# DUT.net
KiCad netlist of a schematic drawn in Altium Designer
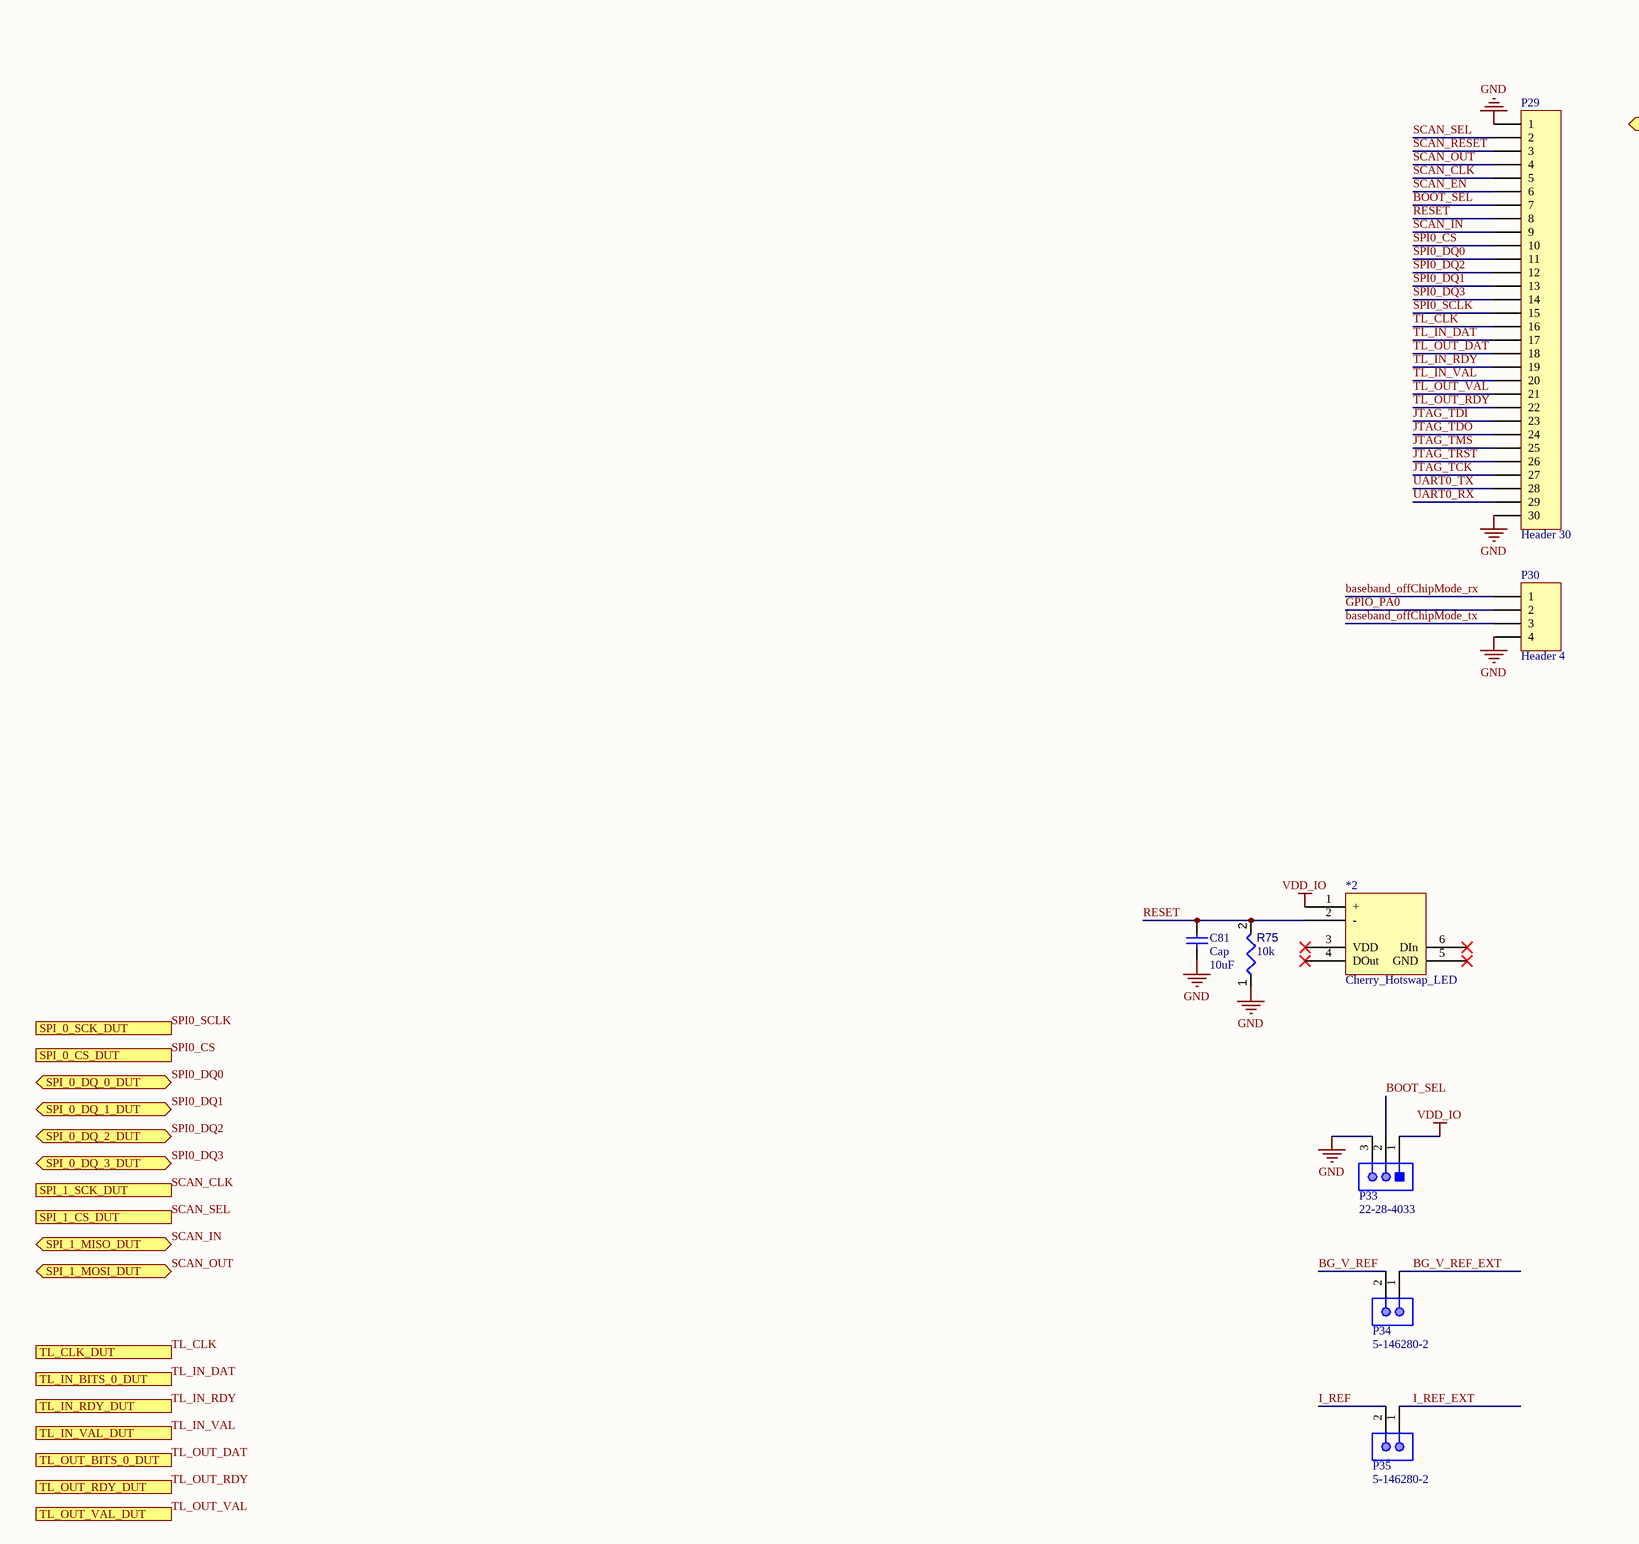
[diagram p0: DUT.SchDoc, top left]
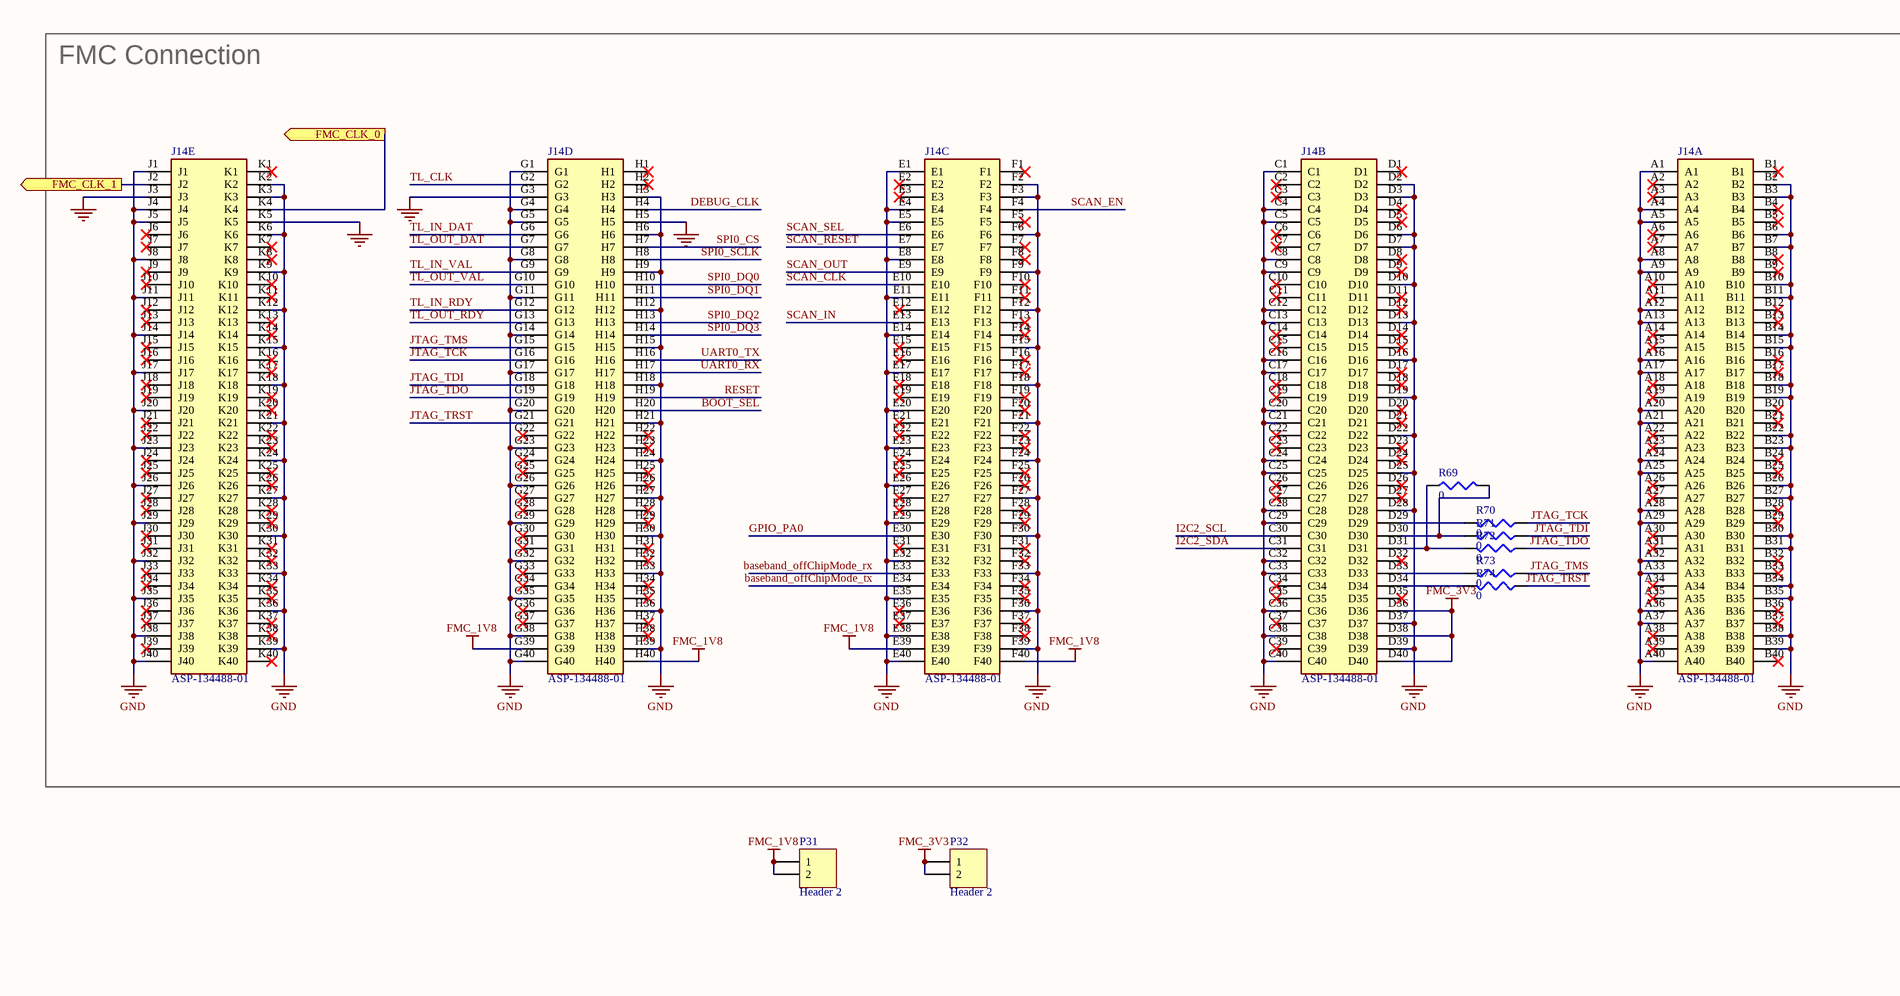
[diagram p1: DUT.SchDoc, top right]
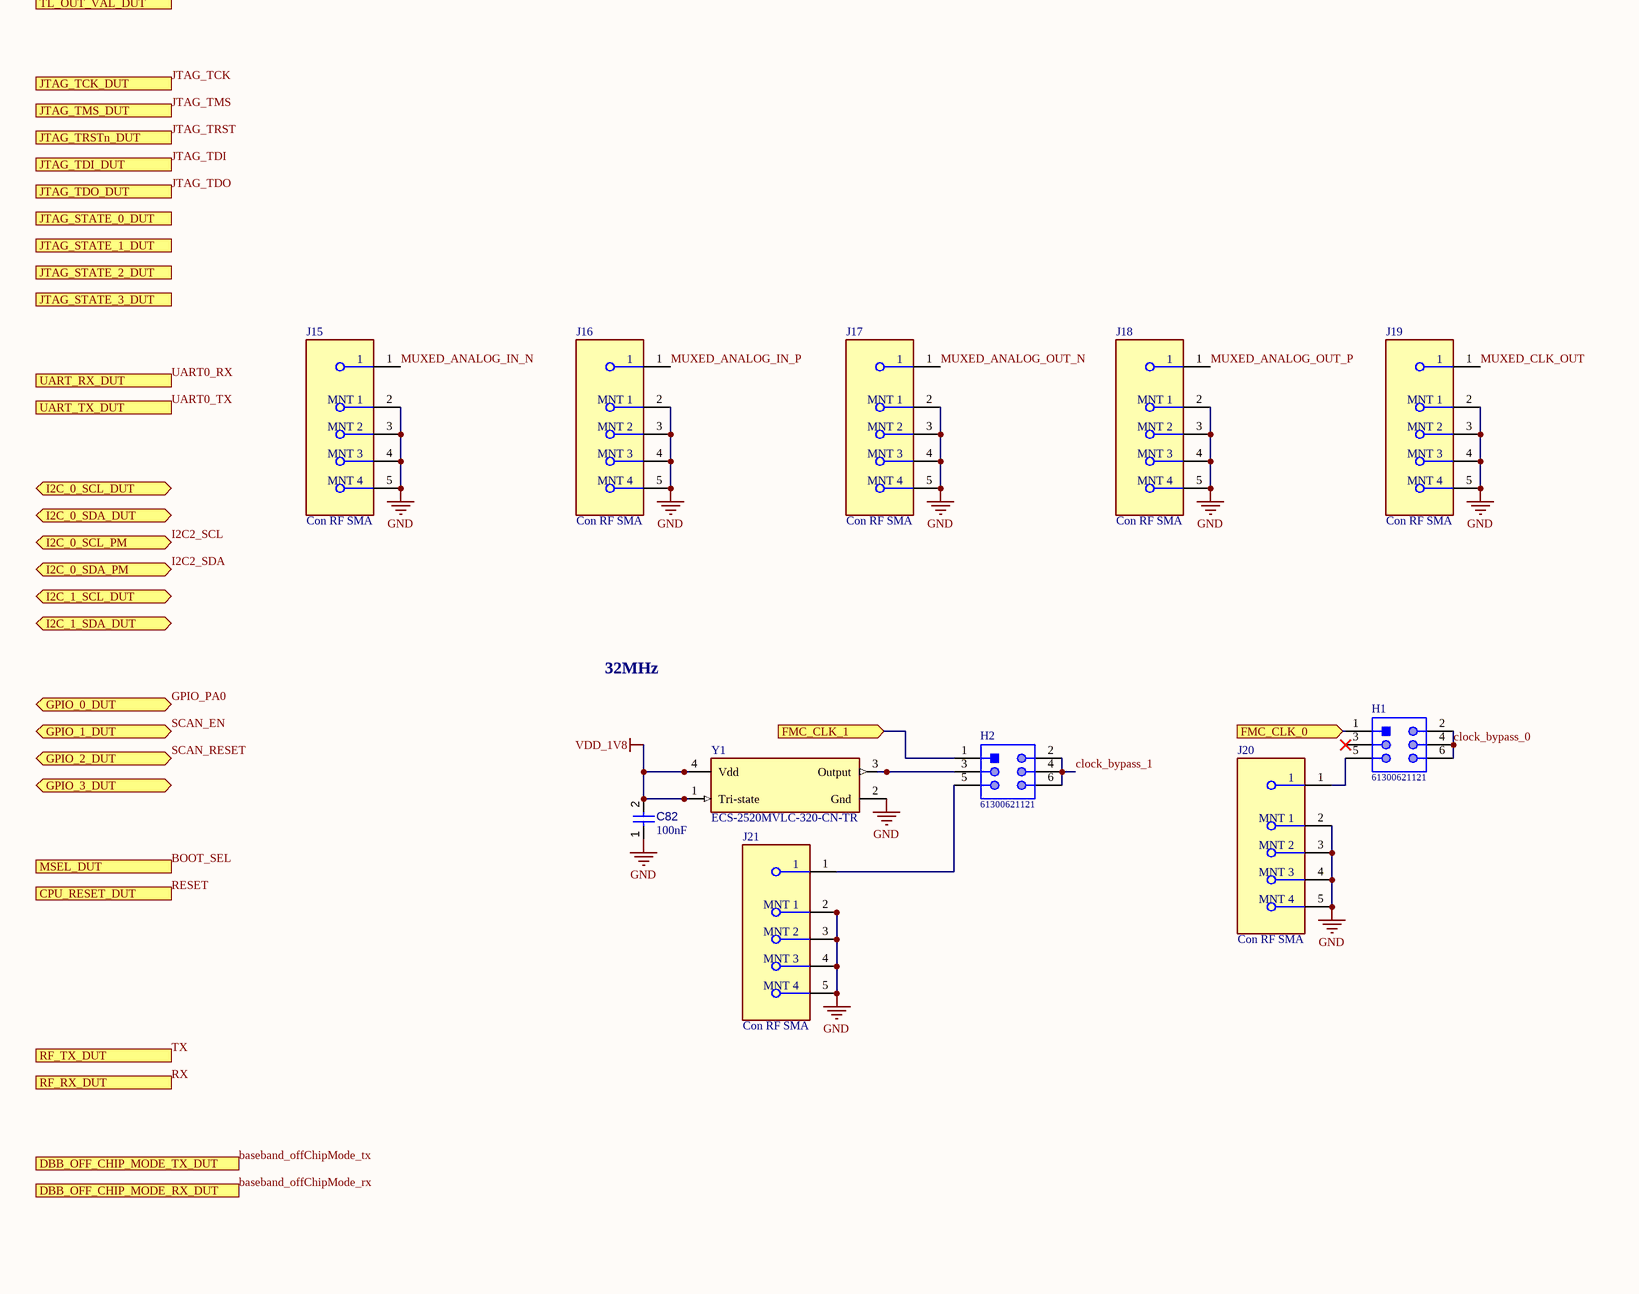
[diagram p2: DUT.SchDoc, bottom left]
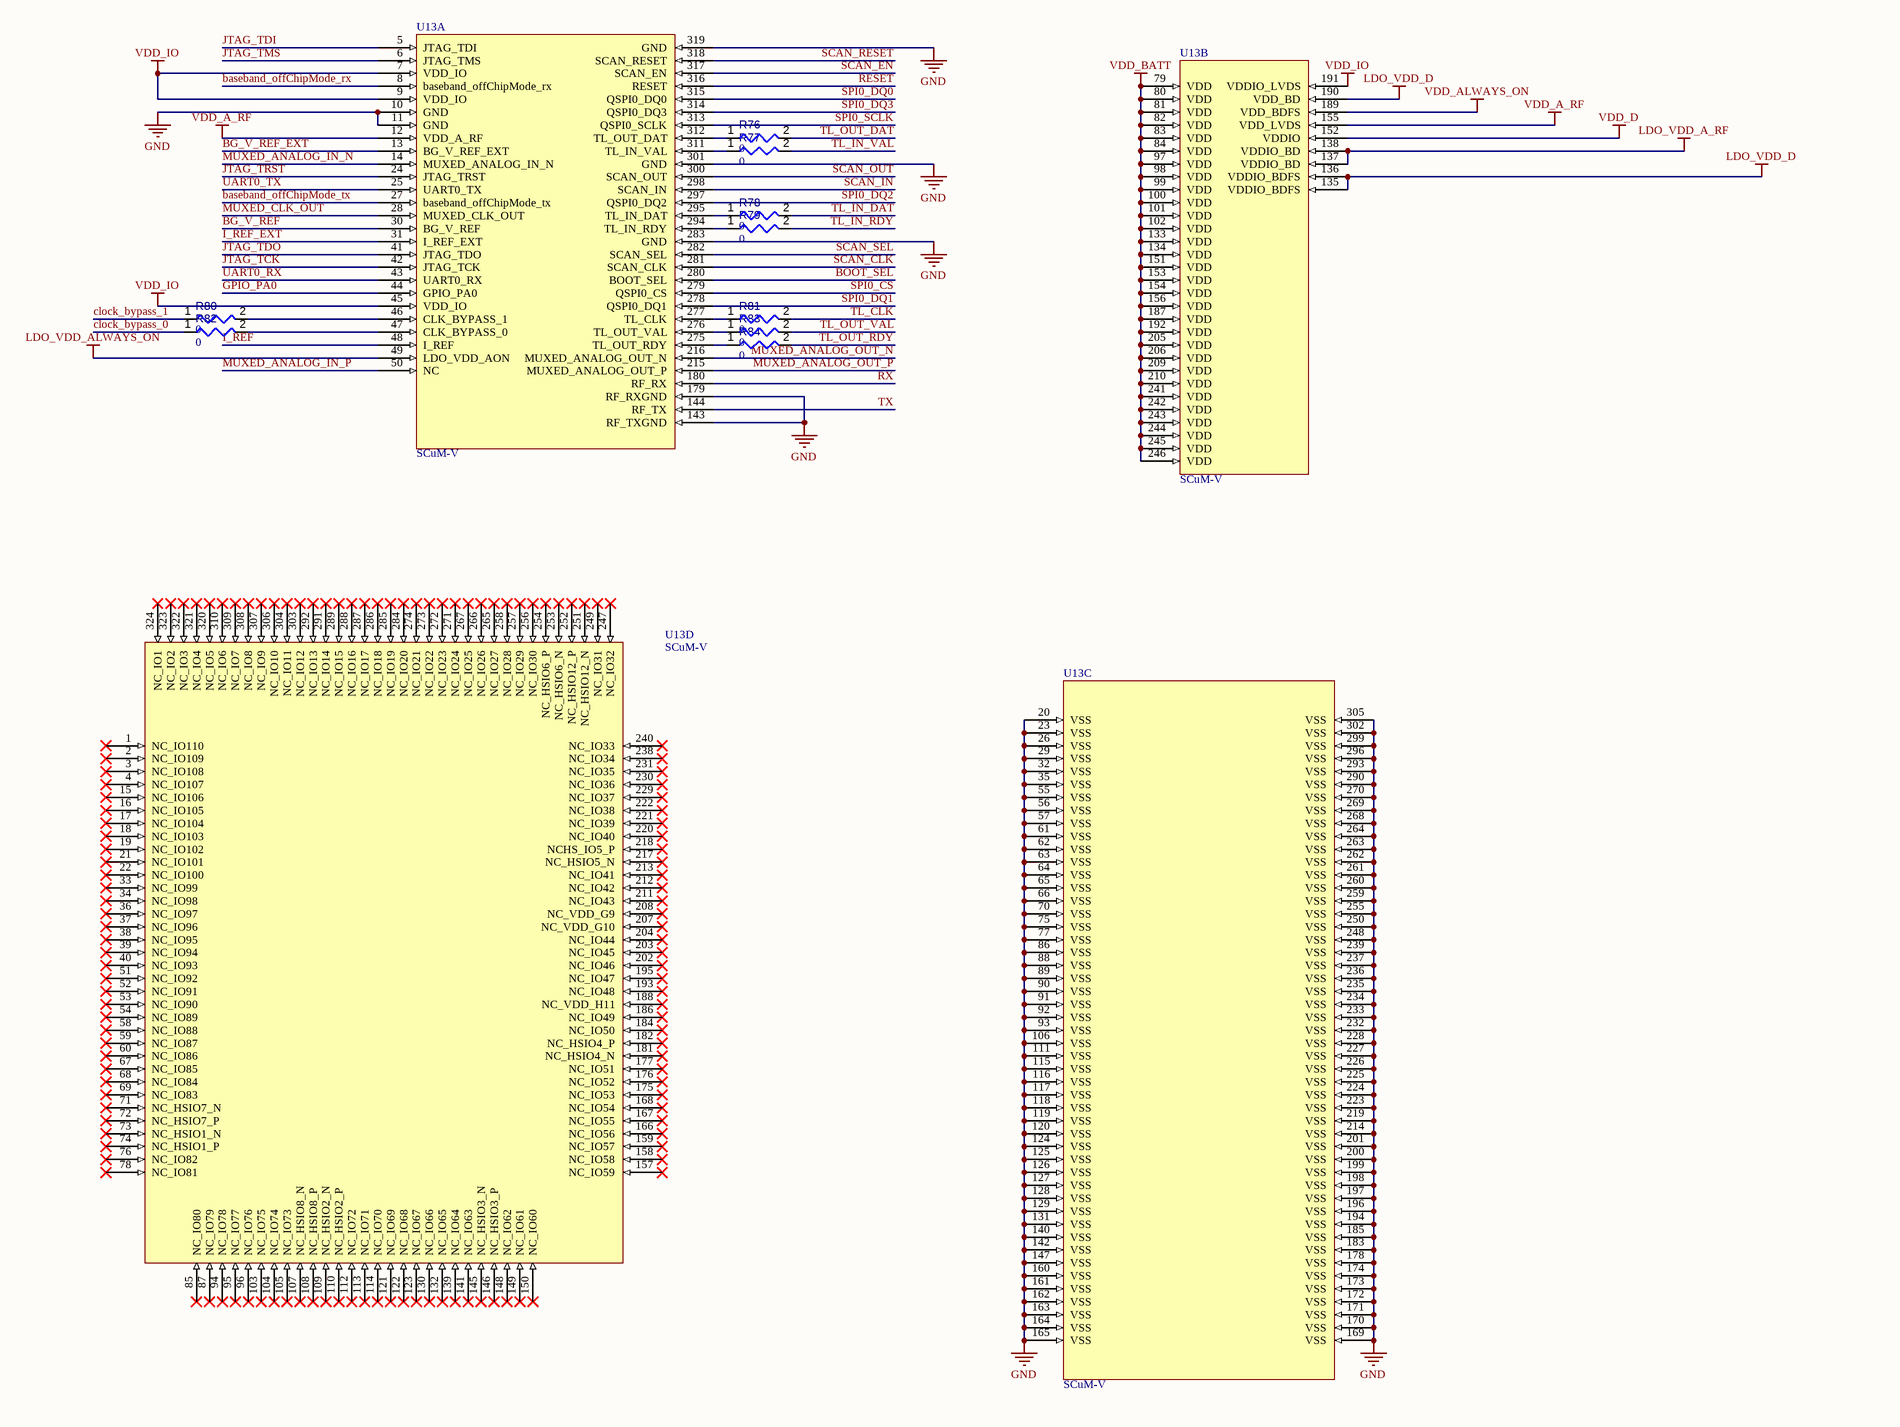
[diagram p3: DUT.SchDoc, bottom right]

(export (version "E")
  (design (tool "Eeschema 10.0.6"))
  (components
    (comp (ref "*2")
      (value "Cherry_Hotswap_LED")
      (footprint "New footprint 1")
      (libsource (lib "EE194 Fall2022") (part "Cherry_Hotswap_LED-Symbol-1"))
    )
    (comp (ref "C81")
      (value "Cap")
      (footprint "0805")
      (description "Capacitor")
      (fields (field (name "ALTIUM_VALUE") "10uF") (field (name "PUBLISHER") "Altium Limited"))
      (libsource (lib "Miscellaneous Devices") (part "Cap"))
    )
    (comp (ref "C82")
      (value "100nF")
      (footprint "CAPC1608X90X40NL10T20")
      (description "Chip Capacitor, 100 nF, +/- 10%, 50 V, 0603 (1608 Metric)")
      (fields (field (name "TOLERANCE") "10%") (field (name "Comment") "Capacitor 100 nF +/-10% 50 V 0603"))
      (libsource (lib "EE194 Fall2022") (part "CAP-NP-2"))
    )
    (comp (ref "H1")
      (value "61300621121")
      (footprint "61300621121")
      (description "THT Vertical Pin Header WR-PHD, Pitch 2.54 mm, Dual Row, 6 pins")
      (fields (field (name "MANUFACTURER") "Wurth Elektronik") (field (name "PUBLISHER") "WurthElektronik"))
      (libsource (lib "Altium Content Vault") (part "WE-CN-2P-M-R6"))
    )
    (comp (ref "H2")
      (value "61300621121")
      (footprint "61300621121")
      (description "THT Vertical Pin Header WR-PHD, Pitch 2.54 mm, Dual Row, 6 pins")
      (fields (field (name "MANUFACTURER") "Wurth Elektronik") (field (name "PUBLISHER") "WurthElektronik"))
      (libsource (lib "Altium Content Vault") (part "WE-CN-2P-M-R6"))
    )
    (comp (ref "J14")
      (value "ASP-134488-01")
      (footprint "SAMTEC_ASP-134488-01")
      (description "Board-To-Board Connector, Vita 57 XMC, ASP Series, Surface Mount, Header, 400, 1.27 mm")
      (libsource (lib "EE194 Fall2022") (part "ASP-134488-01"))
    )
    (comp (ref "J15")
      (value "Con RF SMA")
      (footprint "FP-RF2-04A-T-00-50-G-MFG")
      (description "CONN SMA JACK STR 50 OHM PCB")
      (libsource (lib "Altium Content Vault") (part "c65b8a639cdaef1819ea20b5466f8fa"))
    )
    (comp (ref "J16")
      (value "Con RF SMA")
      (footprint "FP-RF2-04A-T-00-50-G-MFG")
      (description "CONN SMA JACK STR 50 OHM PCB")
      (libsource (lib "Altium Content Vault") (part "c65b8a639cdaef1819ea20b5466f8fa"))
    )
    (comp (ref "J17")
      (value "Con RF SMA")
      (footprint "FP-RF2-04A-T-00-50-G-MFG")
      (description "CONN SMA JACK STR 50 OHM PCB")
      (libsource (lib "Altium Content Vault") (part "c65b8a639cdaef1819ea20b5466f8fa"))
    )
    (comp (ref "J18")
      (value "Con RF SMA")
      (footprint "FP-RF2-04A-T-00-50-G-MFG")
      (description "CONN SMA JACK STR 50 OHM PCB")
      (libsource (lib "Altium Content Vault") (part "c65b8a639cdaef1819ea20b5466f8fa"))
    )
    (comp (ref "J19")
      (value "Con RF SMA")
      (footprint "FP-RF2-04A-T-00-50-G-MFG")
      (description "CONN SMA JACK STR 50 OHM PCB")
      (libsource (lib "Altium Content Vault") (part "c65b8a639cdaef1819ea20b5466f8fa"))
    )
    (comp (ref "J20")
      (value "Con RF SMA")
      (footprint "FP-RF2-04A-T-00-50-G-MFG")
      (description "CONN SMA JACK STR 50 OHM PCB")
      (libsource (lib "Altium Content Vault") (part "c65b8a639cdaef1819ea20b5466f8fa"))
    )
    (comp (ref "J21")
      (value "Con RF SMA")
      (footprint "FP-RF2-04A-T-00-50-G-MFG")
      (description "CONN SMA JACK STR 50 OHM PCB")
      (libsource (lib "Altium Content Vault") (part "c65b8a639cdaef1819ea20b5466f8fa"))
    )
    (comp (ref "P29")
      (value "Header 30")
      (footprint "HDR1X30")
      (description "Header, 30-Pin")
      (fields (field (name "PUBLISHER") "Altium Limited"))
      (libsource (lib "Miscellaneous Connectors") (part "Header 30"))
    )
    (comp (ref "P30")
      (value "Header 4")
      (footprint "HDR1X4")
      (description "Header, 4-Pin")
      (fields (field (name "PUBLISHER") "Altium Limited"))
      (libsource (lib "Miscellaneous Connectors") (part "Header 4"))
    )
    (comp (ref "P31")
      (value "Header 2")
      (footprint "HDR1X2")
      (description "Header, 2-Pin")
      (fields (field (name "PUBLISHER") "Altium Limited"))
      (libsource (lib "Miscellaneous Connectors") (part "Header 2"))
    )
    (comp (ref "P32")
      (value "Header 2")
      (footprint "HDR1X2")
      (description "Header, 2-Pin")
      (fields (field (name "PUBLISHER") "Altium Limited"))
      (libsource (lib "Miscellaneous Connectors") (part "Header 2"))
    )
    (comp (ref "P33")
      (value "22-28-4033")
      (footprint "MOLX-22-28-4033_V")
      (description "Male Header, Pitch 2.54 mm, 1 x 3 Position, Height 8.38 mm, Tail Length 3.18 mm, RoHS, Bulk")
      (fields (field (name "MANUFACTURER") "Molex"))
      (libsource (lib "Altium Content Vault") (part "CN-1P-M-R3"))
    )
    (comp (ref "P34")
      (value "5-146280-2")
      (footprint "TECO-5-146280-2_V")
      (fields (field (name "MANUFACTURER") "TE Connectivity"))
      (libsource (lib "Altium Content Vault") (part "CN-1P-M-R2"))
    )
    (comp (ref "P35")
      (value "5-146280-2")
      (footprint "TECO-5-146280-2_V")
      (fields (field (name "MANUFACTURER") "TE Connectivity"))
      (libsource (lib "Altium Content Vault") (part "CN-1P-M-R2"))
    )
    (comp (ref "R69")
      (value "0")
      (footprint "BWRC:0603")
      (description "0 0603")
      (libsource (lib "BWRC") (part "DISCRETE_R"))
    )
    (comp (ref "R70")
      (value "0")
      (footprint "BWRC:0603")
      (description "0 0603")
      (libsource (lib "BWRC") (part "DISCRETE_R"))
    )
    (comp (ref "R71")
      (value "0")
      (footprint "BWRC:0603")
      (description "0 0603")
      (libsource (lib "BWRC") (part "DISCRETE_R"))
    )
    (comp (ref "R72")
      (value "0")
      (footprint "BWRC:0603")
      (description "0 0603")
      (libsource (lib "BWRC") (part "DISCRETE_R"))
    )
    (comp (ref "R73")
      (value "0")
      (footprint "BWRC:0603")
      (description "0 0603")
      (libsource (lib "BWRC") (part "DISCRETE_R"))
    )
    (comp (ref "R74")
      (value "0")
      (footprint "BWRC:0603")
      (description "0 0603")
      (libsource (lib "BWRC") (part "DISCRETE_R"))
    )
    (comp (ref "R75")
      (value "10k")
      (footprint "RESC1608X55X25ML10T15")
      (description "Chip Resistor, 10 KOhm, +/- 1%, 01 W, -55 to 155 degC, 0603 (1608 Metric)")
      (fields (field (name "POWER") "100mW") (field (name "TOLERANCE") "1%"))
      (libsource (lib "EE194 Fall2022") (part "RES-2"))
    )
    (comp (ref "R76")
      (value "0")
      (footprint "RESC0402(1005)_L")
      (description "Jumper 0402 (1005 Metric)")
      (fields (field (name "Comment") "0R2J"))
      (libsource (lib "EE194 Fall2022") (part "0R2J"))
    )
    (comp (ref "R77")
      (value "0")
      (footprint "RESC0402(1005)_L")
      (description "Jumper 0402 (1005 Metric)")
      (fields (field (name "Comment") "0R2J"))
      (libsource (lib "EE194 Fall2022") (part "0R2J"))
    )
    (comp (ref "R78")
      (value "0")
      (footprint "RESC0402(1005)_L")
      (description "Jumper 0402 (1005 Metric)")
      (fields (field (name "Comment") "0R2J"))
      (libsource (lib "EE194 Fall2022") (part "0R2J"))
    )
    (comp (ref "R79")
      (value "0")
      (footprint "RESC0402(1005)_L")
      (description "Jumper 0402 (1005 Metric)")
      (fields (field (name "Comment") "0R2J"))
      (libsource (lib "EE194 Fall2022") (part "0R2J"))
    )
    (comp (ref "R80")
      (value "0")
      (footprint "RESC0402(1005)_L")
      (description "Jumper 0402 (1005 Metric)")
      (fields (field (name "Comment") "0R2J"))
      (libsource (lib "EE194 Fall2022") (part "0R2J"))
    )
    (comp (ref "R81")
      (value "0")
      (footprint "RESC0402(1005)_L")
      (description "Jumper 0402 (1005 Metric)")
      (fields (field (name "Comment") "0R2J"))
      (libsource (lib "EE194 Fall2022") (part "0R2J"))
    )
    (comp (ref "R82")
      (value "0")
      (footprint "RESC0402(1005)_L")
      (description "Jumper 0402 (1005 Metric)")
      (fields (field (name "Comment") "0R2J"))
      (libsource (lib "EE194 Fall2022") (part "0R2J"))
    )
    (comp (ref "R83")
      (value "0")
      (footprint "RESC0402(1005)_L")
      (description "Jumper 0402 (1005 Metric)")
      (fields (field (name "Comment") "0R2J"))
      (libsource (lib "EE194 Fall2022") (part "0R2J"))
    )
    (comp (ref "R84")
      (value "0")
      (footprint "RESC0402(1005)_L")
      (description "Jumper 0402 (1005 Metric)")
      (fields (field (name "Comment") "0R2J"))
      (libsource (lib "EE194 Fall2022") (part "0R2J"))
    )
    (comp (ref "U13")
      (value "SCuM-V")
      (footprint "BGA324x18")
      (description "SCuM-V chip from Sp22 Tapeout class")
      (libsource (lib "EE194 Fall2022") (part "General"))
    )
    (comp (ref "Y1")
      (value "ECS-2520MVLC-320-CN-TR")
      (footprint "FP-ECS-2520MVLC-MFG")
      (description "XTAL OSC XO 16MHZ CMOS SMD")
      (libsource (lib "Altium Content Vault") (part "4bc2eaef2be8e5a10e07867ed8ca430"))
    )
  )
  (nets
    (net (code "1") (name "/BG_V_REF") (class "Default")
      (node (ref "P34") (pin "2") (pinfunction "2_2") (pintype "passive"))
      (node (ref "U13") (pin "30") (pinfunction "BG_V_REF_30") (pintype "input"))
    )
    (net (code "2") (name "/BG_V_REF_EXT") (class "Default")
      (node (ref "P34") (pin "1") (pinfunction "1_1") (pintype "passive"))
      (node (ref "U13") (pin "13") (pinfunction "BG_V_REF_EXT_13") (pintype "input"))
    )
    (net (code "3") (name "/BOOT_SEL") (class "Default")
      (node (ref "J14") (pin "H20") (pinfunction "H20_H20") (pintype "passive"))
      (node (ref "P29") (pin "7") (pinfunction "7_7") (pintype "passive"))
      (node (ref "P33") (pin "2") (pinfunction "2_2") (pintype "passive"))
      (node (ref "U13") (pin "280") (pinfunction "BOOT_SEL_280") (pintype "input"))
    )
    (net (code "4") (name "/DEBUG_CLK") (class "Default")
      (node (ref "J14") (pin "H4") (pinfunction "H4_H4") (pintype "passive"))
    )
    (net (code "5") (name "/FMC_CLK_0") (class "Default")
      (node (ref "H1") (pin "1") (pinfunction "1_1") (pintype "passive"))
      (node (ref "J14") (pin "K4") (pinfunction "K4_K4") (pintype "passive"))
    )
    (net (code "6") (name "/FMC_CLK_1") (class "Default")
      (node (ref "H2") (pin "1") (pinfunction "1_1") (pintype "passive"))
      (node (ref "J14") (pin "J2") (pinfunction "J2_J2") (pintype "passive"))
    )
    (net (code "8") (name "/GPIO_PA0") (class "Default")
      (node (ref "J14") (pin "E30") (pinfunction "E30_E30") (pintype "passive"))
      (node (ref "P30") (pin "2") (pinfunction "2_2") (pintype "passive"))
      (node (ref "U13") (pin "44") (pinfunction "GPIO_PA0_44") (pintype "input"))
    )
    (net (code "9") (name "/I2C2_SCL") (class "Default")
      (node (ref "J14") (pin "C30") (pinfunction "C30_C30") (pintype "passive"))
    )
    (net (code "10") (name "/I2C2_SDA") (class "Default")
      (node (ref "J14") (pin "C31") (pinfunction "C31_C31") (pintype "passive"))
    )
    (net (code "15") (name "/I_REF") (class "Default")
      (node (ref "P35") (pin "2") (pinfunction "2_2") (pintype "passive"))
      (node (ref "U13") (pin "48") (pinfunction "I_REF_48") (pintype "input"))
    )
    (net (code "16") (name "/I_REF_EXT") (class "Default")
      (node (ref "P35") (pin "1") (pinfunction "1_1") (pintype "passive"))
      (node (ref "U13") (pin "31") (pinfunction "I_REF_EXT_31") (pintype "input"))
    )
    (net (code "21") (name "/JTAG_TCK") (class "Default")
      (node (ref "J14") (pin "G16") (pinfunction "G16_G16") (pintype "passive"))
      (node (ref "P29") (pin "27") (pinfunction "27_27") (pintype "passive"))
      (node (ref "R70") (pin "2") (pinfunction "2_2") (pintype "passive"))
      (node (ref "U13") (pin "42") (pinfunction "JTAG_TCK_42") (pintype "input"))
    )
    (net (code "22") (name "/JTAG_TDI") (class "Default")
      (node (ref "J14") (pin "G18") (pinfunction "G18_G18") (pintype "passive"))
      (node (ref "P29") (pin "23") (pinfunction "23_23") (pintype "passive"))
      (node (ref "R71") (pin "2") (pinfunction "2_2") (pintype "passive"))
      (node (ref "U13") (pin "5") (pinfunction "JTAG_TDI_5") (pintype "input"))
    )
    (net (code "23") (name "/JTAG_TDO") (class "Default")
      (node (ref "J14") (pin "G19") (pinfunction "G19_G19") (pintype "passive"))
      (node (ref "P29") (pin "24") (pinfunction "24_24") (pintype "passive"))
      (node (ref "R72") (pin "2") (pinfunction "2_2") (pintype "passive"))
      (node (ref "U13") (pin "41") (pinfunction "JTAG_TDO_41") (pintype "input"))
    )
    (net (code "24") (name "/JTAG_TMS") (class "Default")
      (node (ref "J14") (pin "G15") (pinfunction "G15_G15") (pintype "passive"))
      (node (ref "P29") (pin "25") (pinfunction "25_25") (pintype "passive"))
      (node (ref "R73") (pin "2") (pinfunction "2_2") (pintype "passive"))
      (node (ref "U13") (pin "6") (pinfunction "JTAG_TMS_6") (pintype "input"))
    )
    (net (code "25") (name "/JTAG_TRST") (class "Default")
      (node (ref "J14") (pin "G21") (pinfunction "G21_G21") (pintype "passive"))
      (node (ref "P29") (pin "26") (pinfunction "26_26") (pintype "passive"))
      (node (ref "R74") (pin "2") (pinfunction "2_2") (pintype "passive"))
      (node (ref "U13") (pin "24") (pinfunction "JTAG_TRST_24") (pintype "input"))
    )
    (net (code "26") (name "/MUXED_ANALOG_IN_N") (class "Default")
      (node (ref "J15") (pin "1") (pinfunction "1_1") (pintype "passive"))
      (node (ref "U13") (pin "14") (pinfunction "MUXED_ANALOG_IN_N_14") (pintype "input"))
    )
    (net (code "27") (name "/MUXED_ANALOG_IN_P") (class "Default")
      (node (ref "J16") (pin "1") (pinfunction "1_1") (pintype "passive"))
      (node (ref "U13") (pin "50") (pinfunction "NC_50") (pintype "input"))
    )
    (net (code "28") (name "/MUXED_ANALOG_OUT_N") (class "Default")
      (node (ref "J17") (pin "1") (pinfunction "1_1") (pintype "passive"))
      (node (ref "U13") (pin "216") (pinfunction "MUXED_ANALOG_OUT_N_216") (pintype "input"))
    )
    (net (code "29") (name "/MUXED_ANALOG_OUT_P") (class "Default")
      (node (ref "J18") (pin "1") (pinfunction "1_1") (pintype "passive"))
      (node (ref "U13") (pin "215") (pinfunction "MUXED_ANALOG_OUT_P_215") (pintype "input"))
    )
    (net (code "30") (name "/MUXED_CLK_OUT") (class "Default")
      (node (ref "J19") (pin "1") (pinfunction "1_1") (pintype "passive"))
      (node (ref "U13") (pin "28") (pinfunction "MUXED_CLK_OUT_28") (pintype "input"))
    )
    (net (code "31") (name "/RESET") (class "Default")
      (node (ref "*2") (pin "2") (pinfunction "-_2") (pintype "passive"))
      (node (ref "C81") (pin "2") (pinfunction "2_2") (pintype "passive"))
      (node (ref "J14") (pin "H19") (pinfunction "H19_H19") (pintype "passive"))
      (node (ref "P29") (pin "8") (pinfunction "8_8") (pintype "passive"))
      (node (ref "R75") (pin "2") (pinfunction "2_2") (pintype "passive"))
      (node (ref "U13") (pin "316") (pinfunction "RESET_316") (pintype "input"))
    )
    (net (code "32") (name "/RX") (class "Default")
      (node (ref "U13") (pin "180") (pinfunction "RF_RX_180") (pintype "input"))
    )
    (net (code "33") (name "/SCAN_CLK") (class "Default")
      (node (ref "J14") (pin "E10") (pinfunction "E10_E10") (pintype "passive"))
      (node (ref "P29") (pin "5") (pinfunction "5_5") (pintype "passive"))
      (node (ref "U13") (pin "281") (pinfunction "SCAN_CLK_281") (pintype "input"))
    )
    (net (code "34") (name "/SCAN_EN") (class "Default")
      (node (ref "J14") (pin "F4") (pinfunction "F4_F4") (pintype "passive"))
      (node (ref "P29") (pin "6") (pinfunction "6_6") (pintype "passive"))
      (node (ref "U13") (pin "317") (pinfunction "SCAN_EN_317") (pintype "input"))
    )
    (net (code "35") (name "/SCAN_IN") (class "Default")
      (node (ref "J14") (pin "E13") (pinfunction "E13_E13") (pintype "passive"))
      (node (ref "P29") (pin "9") (pinfunction "9_9") (pintype "passive"))
      (node (ref "U13") (pin "298") (pinfunction "SCAN_IN_298") (pintype "input"))
    )
    (net (code "36") (name "/SCAN_OUT") (class "Default")
      (node (ref "J14") (pin "E9") (pinfunction "E9_E9") (pintype "passive"))
      (node (ref "P29") (pin "4") (pinfunction "4_4") (pintype "passive"))
      (node (ref "U13") (pin "300") (pinfunction "SCAN_OUT_300") (pintype "input"))
    )
    (net (code "37") (name "/SCAN_RESET") (class "Default")
      (node (ref "J14") (pin "E7") (pinfunction "E7_E7") (pintype "passive"))
      (node (ref "P29") (pin "3") (pinfunction "3_3") (pintype "passive"))
      (node (ref "U13") (pin "318") (pinfunction "SCAN_RESET_318") (pintype "input"))
    )
    (net (code "38") (name "/SCAN_SEL") (class "Default")
      (node (ref "J14") (pin "E6") (pinfunction "E6_E6") (pintype "passive"))
      (node (ref "P29") (pin "2") (pinfunction "2_2") (pintype "passive"))
      (node (ref "U13") (pin "282") (pinfunction "SCAN_SEL_282") (pintype "input"))
    )
    (net (code "39") (name "/SPI0_CS") (class "Default")
      (node (ref "J14") (pin "H7") (pinfunction "H7_H7") (pintype "passive"))
      (node (ref "P29") (pin "10") (pinfunction "10_10") (pintype "passive"))
      (node (ref "U13") (pin "279") (pinfunction "QSPI0_CS_279") (pintype "input"))
    )
    (net (code "40") (name "/SPI0_DQ0") (class "Default")
      (node (ref "J14") (pin "H10") (pinfunction "H10_H10") (pintype "passive"))
      (node (ref "P29") (pin "11") (pinfunction "11_11") (pintype "passive"))
      (node (ref "U13") (pin "315") (pinfunction "QSPI0_DQ0_315") (pintype "input"))
    )
    (net (code "41") (name "/SPI0_DQ1") (class "Default")
      (node (ref "J14") (pin "H11") (pinfunction "H11_H11") (pintype "passive"))
      (node (ref "P29") (pin "13") (pinfunction "13_13") (pintype "passive"))
      (node (ref "U13") (pin "278") (pinfunction "QSPI0_DQ1_278") (pintype "input"))
    )
    (net (code "42") (name "/SPI0_DQ2") (class "Default")
      (node (ref "J14") (pin "H13") (pinfunction "H13_H13") (pintype "passive"))
      (node (ref "P29") (pin "12") (pinfunction "12_12") (pintype "passive"))
      (node (ref "U13") (pin "297") (pinfunction "QSPI0_DQ2_297") (pintype "input"))
    )
    (net (code "43") (name "/SPI0_DQ3") (class "Default")
      (node (ref "J14") (pin "H14") (pinfunction "H14_H14") (pintype "passive"))
      (node (ref "P29") (pin "14") (pinfunction "14_14") (pintype "passive"))
      (node (ref "U13") (pin "314") (pinfunction "QSPI0_DQ3_314") (pintype "input"))
    )
    (net (code "44") (name "/SPI0_SCLK") (class "Default")
      (node (ref "J14") (pin "H8") (pinfunction "H8_H8") (pintype "passive"))
      (node (ref "P29") (pin "15") (pinfunction "15_15") (pintype "passive"))
      (node (ref "U13") (pin "313") (pinfunction "QSPI0_SCLK_313") (pintype "input"))
    )
    (net (code "45") (name "/TL_CLK") (class "Default")
      (node (ref "J14") (pin "G2") (pinfunction "G2_G2") (pintype "passive"))
      (node (ref "P29") (pin "16") (pinfunction "16_16") (pintype "passive"))
      (node (ref "R81") (pin "2") (pinfunction "2_2") (pintype "passive"))
    )
    (net (code "46") (name "/TL_IN_DAT") (class "Default")
      (node (ref "J14") (pin "G6") (pinfunction "G6_G6") (pintype "passive"))
      (node (ref "P29") (pin "17") (pinfunction "17_17") (pintype "passive"))
      (node (ref "R78") (pin "2") (pinfunction "2_2") (pintype "passive"))
    )
    (net (code "47") (name "/TL_IN_RDY") (class "Default")
      (node (ref "J14") (pin "G12") (pinfunction "G12_G12") (pintype "passive"))
      (node (ref "P29") (pin "19") (pinfunction "19_19") (pintype "passive"))
      (node (ref "R79") (pin "2") (pinfunction "2_2") (pintype "passive"))
    )
    (net (code "48") (name "/TL_IN_VAL") (class "Default")
      (node (ref "J14") (pin "G9") (pinfunction "G9_G9") (pintype "passive"))
      (node (ref "P29") (pin "20") (pinfunction "20_20") (pintype "passive"))
      (node (ref "R77") (pin "2") (pinfunction "2_2") (pintype "passive"))
    )
    (net (code "49") (name "/TL_OUT_DAT") (class "Default")
      (node (ref "J14") (pin "G7") (pinfunction "G7_G7") (pintype "passive"))
      (node (ref "P29") (pin "18") (pinfunction "18_18") (pintype "passive"))
      (node (ref "R76") (pin "2") (pinfunction "2_2") (pintype "passive"))
    )
    (net (code "50") (name "/TL_OUT_RDY") (class "Default")
      (node (ref "J14") (pin "G13") (pinfunction "G13_G13") (pintype "passive"))
      (node (ref "P29") (pin "22") (pinfunction "22_22") (pintype "passive"))
      (node (ref "R84") (pin "2") (pinfunction "2_2") (pintype "passive"))
    )
    (net (code "51") (name "/TL_OUT_VAL") (class "Default")
      (node (ref "J14") (pin "G10") (pinfunction "G10_G10") (pintype "passive"))
      (node (ref "P29") (pin "21") (pinfunction "21_21") (pintype "passive"))
      (node (ref "R83") (pin "2") (pinfunction "2_2") (pintype "passive"))
    )
    (net (code "52") (name "/TX") (class "Default")
      (node (ref "U13") (pin "144") (pinfunction "RF_TX_144") (pintype "input"))
    )
    (net (code "53") (name "/UART0_RX") (class "Default")
      (node (ref "J14") (pin "H17") (pinfunction "H17_H17") (pintype "passive"))
      (node (ref "P29") (pin "29") (pinfunction "29_29") (pintype "passive"))
      (node (ref "U13") (pin "43") (pinfunction "UART0_RX_43") (pintype "input"))
    )
    (net (code "54") (name "/UART0_TX") (class "Default")
      (node (ref "J14") (pin "H16") (pinfunction "H16_H16") (pintype "passive"))
      (node (ref "P29") (pin "28") (pinfunction "28_28") (pintype "passive"))
      (node (ref "U13") (pin "25") (pinfunction "UART0_TX_25") (pintype "input"))
    )
    (net (code "55") (name "/baseband_offChipMode_rx") (class "Default")
      (node (ref "J14") (pin "E33") (pinfunction "E33_E33") (pintype "passive"))
      (node (ref "P30") (pin "1") (pinfunction "1_1") (pintype "passive"))
      (node (ref "U13") (pin "8") (pinfunction "baseband_offChipMode_rx_8") (pintype "input"))
    )
    (net (code "56") (name "/baseband_offChipMode_tx") (class "Default")
      (node (ref "J14") (pin "E34") (pinfunction "E34_E34") (pintype "passive"))
      (node (ref "P30") (pin "3") (pinfunction "3_3") (pintype "passive"))
      (node (ref "U13") (pin "27") (pinfunction "baseband_offChipMode_tx_27") (pintype "input"))
    )
    (net (code "57") (name "/clock_bypass_0") (class "Default")
      (node (ref "H1") (pin "2") (pinfunction "2_2") (pintype "passive"))
      (node (ref "H1") (pin "4") (pinfunction "4_4") (pintype "passive"))
      (node (ref "H1") (pin "6") (pinfunction "6_6") (pintype "passive"))
      (node (ref "R82") (pin "1") (pinfunction "1_1") (pintype "passive"))
    )
    (net (code "58") (name "/clock_bypass_1") (class "Default")
      (node (ref "H2") (pin "2") (pinfunction "2_2") (pintype "passive"))
      (node (ref "H2") (pin "4") (pinfunction "4_4") (pintype "passive"))
      (node (ref "H2") (pin "6") (pinfunction "6_6") (pintype "passive"))
      (node (ref "R80") (pin "1") (pinfunction "1_1") (pintype "passive"))
    )
    (net (code "59") (name "FMC_1V8") (class "Default")
      (node (ref "J14") (pin "E39") (pinfunction "E39_E39") (pintype "passive"))
      (node (ref "J14") (pin "F40") (pinfunction "F40_F40") (pintype "passive"))
      (node (ref "J14") (pin "G39") (pinfunction "G39_G39") (pintype "passive"))
      (node (ref "J14") (pin "H40") (pinfunction "H40_H40") (pintype "passive"))
      (node (ref "P31") (pin "1") (pinfunction "1_1") (pintype "passive"))
      (node (ref "P31") (pin "2") (pinfunction "2_2") (pintype "passive"))
    )
    (net (code "60") (name "FMC_3V3") (class "Default")
      (node (ref "J14") (pin "D36") (pinfunction "D36_D36") (pintype "passive"))
      (node (ref "J14") (pin "D38") (pinfunction "D38_D38") (pintype "passive"))
      (node (ref "J14") (pin "D40") (pinfunction "D40_D40") (pintype "passive"))
      (node (ref "P32") (pin "1") (pinfunction "1_1") (pintype "passive"))
      (node (ref "P32") (pin "2") (pinfunction "2_2") (pintype "passive"))
    )
    (net (code "61") (name "GND") (class "Default")
      (node (ref "C81") (pin "1") (pinfunction "1_1") (pintype "passive"))
      (node (ref "C82") (pin "1") (pinfunction "1_1") (pintype "passive"))
      (node (ref "J14") (pin "A1") (pinfunction "A1_A1") (pintype "passive"))
      (node (ref "J14") (pin "A12") (pinfunction "A12_A12") (pintype "passive"))
      (node (ref "J14") (pin "A13") (pinfunction "A13_A13") (pintype "passive"))
      (node (ref "J14") (pin "A16") (pinfunction "A16_A16") (pintype "passive"))
      (node (ref "J14") (pin "A17") (pinfunction "A17_A17") (pintype "passive"))
      (node (ref "J14") (pin "A20") (pinfunction "A20_A20") (pintype "passive"))
      (node (ref "J14") (pin "A21") (pinfunction "A21_A21") (pintype "passive"))
      (node (ref "J14") (pin "A24") (pinfunction "A24_A24") (pintype "passive"))
      (node (ref "J14") (pin "A25") (pinfunction "A25_A25") (pintype "passive"))
      (node (ref "J14") (pin "A28") (pinfunction "A28_A28") (pintype "passive"))
      (node (ref "J14") (pin "A29") (pinfunction "A29_A29") (pintype "passive"))
      (node (ref "J14") (pin "A32") (pinfunction "A32_A32") (pintype "passive"))
      (node (ref "J14") (pin "A33") (pinfunction "A33_A33") (pintype "passive"))
      (node (ref "J14") (pin "A36") (pinfunction "A36_A36") (pintype "passive"))
      (node (ref "J14") (pin "A37") (pinfunction "A37_A37") (pintype "passive"))
      (node (ref "J14") (pin "A4") (pinfunction "A4_A4") (pintype "passive"))
      (node (ref "J14") (pin "A40") (pinfunction "A40_A40") (pintype "passive"))
      (node (ref "J14") (pin "A5") (pinfunction "A5_A5") (pintype "passive"))
      (node (ref "J14") (pin "A8") (pinfunction "A8_A8") (pintype "passive"))
      (node (ref "J14") (pin "A9") (pinfunction "A9_A9") (pintype "passive"))
      (node (ref "J14") (pin "B10") (pinfunction "B10_B10") (pintype "passive"))
      (node (ref "J14") (pin "B11") (pinfunction "B11_B11") (pintype "passive"))
      (node (ref "J14") (pin "B14") (pinfunction "B14_B14") (pintype "passive"))
      (node (ref "J14") (pin "B15") (pinfunction "B15_B15") (pintype "passive"))
      (node (ref "J14") (pin "B18") (pinfunction "B18_B18") (pintype "passive"))
      (node (ref "J14") (pin "B19") (pinfunction "B19_B19") (pintype "passive"))
      (node (ref "J14") (pin "B2") (pinfunction "B2_B2") (pintype "passive"))
      (node (ref "J14") (pin "B22") (pinfunction "B22_B22") (pintype "passive"))
      (node (ref "J14") (pin "B23") (pinfunction "B23_B23") (pintype "passive"))
      (node (ref "J14") (pin "B26") (pinfunction "B26_B26") (pintype "passive"))
      (node (ref "J14") (pin "B27") (pinfunction "B27_B27") (pintype "passive"))
      (node (ref "J14") (pin "B3") (pinfunction "B3_B3") (pintype "passive"))
      (node (ref "J14") (pin "B30") (pinfunction "B30_B30") (pintype "passive"))
      (node (ref "J14") (pin "B31") (pinfunction "B31_B31") (pintype "passive"))
      (node (ref "J14") (pin "B34") (pinfunction "B34_B34") (pintype "passive"))
      (node (ref "J14") (pin "B35") (pinfunction "B35_B35") (pintype "passive"))
      (node (ref "J14") (pin "B38") (pinfunction "B38_B38") (pintype "passive"))
      (node (ref "J14") (pin "B39") (pinfunction "B39_B39") (pintype "passive"))
      (node (ref "J14") (pin "B6") (pinfunction "B6_B6") (pintype "passive"))
      (node (ref "J14") (pin "B7") (pinfunction "B7_B7") (pintype "passive"))
      (node (ref "J14") (pin "C1") (pinfunction "C1_C1") (pintype "passive"))
      (node (ref "J14") (pin "C12") (pinfunction "C12_C12") (pintype "passive"))
      (node (ref "J14") (pin "C13") (pinfunction "C13_C13") (pintype "passive"))
      (node (ref "J14") (pin "C16") (pinfunction "C16_C16") (pintype "passive"))
      (node (ref "J14") (pin "C17") (pinfunction "C17_C17") (pintype "passive"))
      (node (ref "J14") (pin "C20") (pinfunction "C20_C20") (pintype "passive"))
      (node (ref "J14") (pin "C21") (pinfunction "C21_C21") (pintype "passive"))
      (node (ref "J14") (pin "C24") (pinfunction "C24_C24") (pintype "passive"))
      (node (ref "J14") (pin "C25") (pinfunction "C25_C25") (pintype "passive"))
      (node (ref "J14") (pin "C28") (pinfunction "C28_C28") (pintype "passive"))
      (node (ref "J14") (pin "C29") (pinfunction "C29_C29") (pintype "passive"))
      (node (ref "J14") (pin "C32") (pinfunction "C32_C32") (pintype "passive"))
      (node (ref "J14") (pin "C33") (pinfunction "C33_C33") (pintype "passive"))
      (node (ref "J14") (pin "C36") (pinfunction "C36_C36") (pintype "passive"))
      (node (ref "J14") (pin "C38") (pinfunction "C38_C38") (pintype "passive"))
      (node (ref "J14") (pin "C4") (pinfunction "C4_C4") (pintype "passive"))
      (node (ref "J14") (pin "C40") (pinfunction "C40_C40") (pintype "passive"))
      (node (ref "J14") (pin "C5") (pinfunction "C5_C5") (pintype "passive"))
      (node (ref "J14") (pin "C8") (pinfunction "C8_C8") (pintype "passive"))
      (node (ref "J14") (pin "C9") (pinfunction "C9_C9") (pintype "passive"))
      (node (ref "J14") (pin "D10") (pinfunction "D10_D10") (pintype "passive"))
      (node (ref "J14") (pin "D13") (pinfunction "D13_D13") (pintype "passive"))
      (node (ref "J14") (pin "D16") (pinfunction "D16_D16") (pintype "passive"))
      (node (ref "J14") (pin "D19") (pinfunction "D19_D19") (pintype "passive"))
      (node (ref "J14") (pin "D2") (pinfunction "D2_D2") (pintype "passive"))
      (node (ref "J14") (pin "D22") (pinfunction "D22_D22") (pintype "passive"))
      (node (ref "J14") (pin "D25") (pinfunction "D25_D25") (pintype "passive"))
      (node (ref "J14") (pin "D28") (pinfunction "D28_D28") (pintype "passive"))
      (node (ref "J14") (pin "D3") (pinfunction "D3_D3") (pintype "passive"))
      (node (ref "J14") (pin "D37") (pinfunction "D37_D37") (pintype "passive"))
      (node (ref "J14") (pin "D39") (pinfunction "D39_D39") (pintype "passive"))
      (node (ref "J14") (pin "D6") (pinfunction "D6_D6") (pintype "passive"))
      (node (ref "J14") (pin "D7") (pinfunction "D7_D7") (pintype "passive"))
      (node (ref "J14") (pin "E1") (pinfunction "E1_E1") (pintype "passive"))
      (node (ref "J14") (pin "E11") (pinfunction "E11_E11") (pintype "passive"))
      (node (ref "J14") (pin "E14") (pinfunction "E14_E14") (pintype "passive"))
      (node (ref "J14") (pin "E17") (pinfunction "E17_E17") (pintype "passive"))
      (node (ref "J14") (pin "E20") (pinfunction "E20_E20") (pintype "passive"))
      (node (ref "J14") (pin "E23") (pinfunction "E23_E23") (pintype "passive"))
      (node (ref "J14") (pin "E26") (pinfunction "E26_E26") (pintype "passive"))
      (node (ref "J14") (pin "E29") (pinfunction "E29_E29") (pintype "passive"))
      (node (ref "J14") (pin "E32") (pinfunction "E32_E32") (pintype "passive"))
      (node (ref "J14") (pin "E35") (pinfunction "E35_E35") (pintype "passive"))
      (node (ref "J14") (pin "E38") (pinfunction "E38_E38") (pintype "passive"))
      (node (ref "J14") (pin "E4") (pinfunction "E4_E4") (pintype "passive"))
      (node (ref "J14") (pin "E40") (pinfunction "E40_E40") (pintype "passive"))
      (node (ref "J14") (pin "E5") (pinfunction "E5_E5") (pintype "passive"))
      (node (ref "J14") (pin "E8") (pinfunction "E8_E8") (pintype "passive"))
      (node (ref "J14") (pin "F12") (pinfunction "F12_F12") (pintype "passive"))
      (node (ref "J14") (pin "F15") (pinfunction "F15_F15") (pintype "passive"))
      (node (ref "J14") (pin "F18") (pinfunction "F18_F18") (pintype "passive"))
      (node (ref "J14") (pin "F2") (pinfunction "F2_F2") (pintype "passive"))
      (node (ref "J14") (pin "F21") (pinfunction "F21_F21") (pintype "passive"))
      (node (ref "J14") (pin "F24") (pinfunction "F24_F24") (pintype "passive"))
      (node (ref "J14") (pin "F27") (pinfunction "F27_F27") (pintype "passive"))
      (node (ref "J14") (pin "F3") (pinfunction "F3_F3") (pintype "passive"))
      (node (ref "J14") (pin "F30") (pinfunction "F30_F30") (pintype "passive"))
      (node (ref "J14") (pin "F33") (pinfunction "F33_F33") (pintype "passive"))
      (node (ref "J14") (pin "F36") (pinfunction "F36_F36") (pintype "passive"))
      (node (ref "J14") (pin "F39") (pinfunction "F39_F39") (pintype "passive"))
      (node (ref "J14") (pin "F6") (pinfunction "F6_F6") (pintype "passive"))
      (node (ref "J14") (pin "F9") (pinfunction "F9_F9") (pintype "passive"))
      (node (ref "J14") (pin "G1") (pinfunction "G1_G1") (pintype "passive"))
      (node (ref "J14") (pin "G11") (pinfunction "G11_G11") (pintype "passive"))
      (node (ref "J14") (pin "G14") (pinfunction "G14_G14") (pintype "passive"))
      (node (ref "J14") (pin "G17") (pinfunction "G17_G17") (pintype "passive"))
      (node (ref "J14") (pin "G20") (pinfunction "G20_G20") (pintype "passive"))
      (node (ref "J14") (pin "G23") (pinfunction "G23_G23") (pintype "passive"))
      (node (ref "J14") (pin "G26") (pinfunction "G26_G26") (pintype "passive"))
      (node (ref "J14") (pin "G29") (pinfunction "G29_G29") (pintype "passive"))
      (node (ref "J14") (pin "G3") (pinfunction "G3_G3") (pintype "passive"))
      (node (ref "J14") (pin "G32") (pinfunction "G32_G32") (pintype "passive"))
      (node (ref "J14") (pin "G35") (pinfunction "G35_G35") (pintype "passive"))
      (node (ref "J14") (pin "G38") (pinfunction "G38_G38") (pintype "passive"))
      (node (ref "J14") (pin "G4") (pinfunction "G4_G4") (pintype "passive"))
      (node (ref "J14") (pin "G40") (pinfunction "G40_G40") (pintype "passive"))
      (node (ref "J14") (pin "G5") (pinfunction "G5_G5") (pintype "passive"))
      (node (ref "J14") (pin "G8") (pinfunction "G8_G8") (pintype "passive"))
      (node (ref "J14") (pin "H12") (pinfunction "H12_H12") (pintype "passive"))
      (node (ref "J14") (pin "H15") (pinfunction "H15_H15") (pintype "passive"))
      (node (ref "J14") (pin "H18") (pinfunction "H18_H18") (pintype "passive"))
      (node (ref "J14") (pin "H21") (pinfunction "H21_H21") (pintype "passive"))
      (node (ref "J14") (pin "H24") (pinfunction "H24_H24") (pintype "passive"))
      (node (ref "J14") (pin "H27") (pinfunction "H27_H27") (pintype "passive"))
      (node (ref "J14") (pin "H3") (pinfunction "H3_H3") (pintype "passive"))
      (node (ref "J14") (pin "H30") (pinfunction "H30_H30") (pintype "passive"))
      (node (ref "J14") (pin "H33") (pinfunction "H33_H33") (pintype "passive"))
      (node (ref "J14") (pin "H36") (pinfunction "H36_H36") (pintype "passive"))
      (node (ref "J14") (pin "H39") (pinfunction "H39_H39") (pintype "passive"))
      (node (ref "J14") (pin "H5") (pinfunction "H5_H5") (pintype "passive"))
      (node (ref "J14") (pin "H6") (pinfunction "H6_H6") (pintype "passive"))
      (node (ref "J14") (pin "H9") (pinfunction "H9_H9") (pintype "passive"))
      (node (ref "J14") (pin "J1") (pinfunction "J1_J1") (pintype "passive"))
      (node (ref "J14") (pin "J11") (pinfunction "J11_J11") (pintype "passive"))
      (node (ref "J14") (pin "J14") (pinfunction "J14_J14") (pintype "passive"))
      (node (ref "J14") (pin "J17") (pinfunction "J17_J17") (pintype "passive"))
      (node (ref "J14") (pin "J20") (pinfunction "J20_J20") (pintype "passive"))
      (node (ref "J14") (pin "J23") (pinfunction "J23_J23") (pintype "passive"))
      (node (ref "J14") (pin "J26") (pinfunction "J26_J26") (pintype "passive"))
      (node (ref "J14") (pin "J29") (pinfunction "J29_J29") (pintype "passive"))
      (node (ref "J14") (pin "J3") (pinfunction "J3_J3") (pintype "passive"))
      (node (ref "J14") (pin "J32") (pinfunction "J32_J32") (pintype "passive"))
      (node (ref "J14") (pin "J35") (pinfunction "J35_J35") (pintype "passive"))
      (node (ref "J14") (pin "J38") (pinfunction "J38_J38") (pintype "passive"))
      (node (ref "J14") (pin "J4") (pinfunction "J4_J4") (pintype "passive"))
      (node (ref "J14") (pin "J40") (pinfunction "J40_J40") (pintype "passive"))
      (node (ref "J14") (pin "J5") (pinfunction "J5_J5") (pintype "passive"))
      (node (ref "J14") (pin "J8") (pinfunction "J8_J8") (pintype "passive"))
      (node (ref "J14") (pin "K12") (pinfunction "K12_K12") (pintype "passive"))
      (node (ref "J14") (pin "K15") (pinfunction "K15_K15") (pintype "passive"))
      (node (ref "J14") (pin "K18") (pinfunction "K18_K18") (pintype "passive"))
      (node (ref "J14") (pin "K2") (pinfunction "K2_K2") (pintype "passive"))
      (node (ref "J14") (pin "K21") (pinfunction "K21_K21") (pintype "passive"))
      (node (ref "J14") (pin "K24") (pinfunction "K24_K24") (pintype "passive"))
      (node (ref "J14") (pin "K27") (pinfunction "K27_K27") (pintype "passive"))
      (node (ref "J14") (pin "K3") (pinfunction "K3_K3") (pintype "passive"))
      (node (ref "J14") (pin "K30") (pinfunction "K30_K30") (pintype "passive"))
      (node (ref "J14") (pin "K33") (pinfunction "K33_K33") (pintype "passive"))
      (node (ref "J14") (pin "K36") (pinfunction "K36_K36") (pintype "passive"))
      (node (ref "J14") (pin "K39") (pinfunction "K39_K39") (pintype "passive"))
      (node (ref "J14") (pin "K5") (pinfunction "K5_K5") (pintype "passive"))
      (node (ref "J14") (pin "K6") (pinfunction "K6_K6") (pintype "passive"))
      (node (ref "J14") (pin "K9") (pinfunction "K9_K9") (pintype "passive"))
      (node (ref "J15") (pin "2") (pinfunction "MNT_1_2") (pintype "passive"))
      (node (ref "J15") (pin "3") (pinfunction "MNT_2_3") (pintype "passive"))
      (node (ref "J15") (pin "4") (pinfunction "MNT_3_4") (pintype "passive"))
      (node (ref "J15") (pin "5") (pinfunction "MNT_4_5") (pintype "passive"))
      (node (ref "J16") (pin "2") (pinfunction "MNT_1_2") (pintype "passive"))
      (node (ref "J16") (pin "3") (pinfunction "MNT_2_3") (pintype "passive"))
      (node (ref "J16") (pin "4") (pinfunction "MNT_3_4") (pintype "passive"))
      (node (ref "J16") (pin "5") (pinfunction "MNT_4_5") (pintype "passive"))
      (node (ref "J17") (pin "2") (pinfunction "MNT_1_2") (pintype "passive"))
      (node (ref "J17") (pin "3") (pinfunction "MNT_2_3") (pintype "passive"))
      (node (ref "J17") (pin "4") (pinfunction "MNT_3_4") (pintype "passive"))
      (node (ref "J17") (pin "5") (pinfunction "MNT_4_5") (pintype "passive"))
      (node (ref "J18") (pin "2") (pinfunction "MNT_1_2") (pintype "passive"))
      (node (ref "J18") (pin "3") (pinfunction "MNT_2_3") (pintype "passive"))
      (node (ref "J18") (pin "4") (pinfunction "MNT_3_4") (pintype "passive"))
      (node (ref "J18") (pin "5") (pinfunction "MNT_4_5") (pintype "passive"))
      (node (ref "J19") (pin "2") (pinfunction "MNT_1_2") (pintype "passive"))
      (node (ref "J19") (pin "3") (pinfunction "MNT_2_3") (pintype "passive"))
      (node (ref "J19") (pin "4") (pinfunction "MNT_3_4") (pintype "passive"))
      (node (ref "J19") (pin "5") (pinfunction "MNT_4_5") (pintype "passive"))
      (node (ref "J20") (pin "2") (pinfunction "MNT_1_2") (pintype "passive"))
      (node (ref "J20") (pin "3") (pinfunction "MNT_2_3") (pintype "passive"))
      (node (ref "J20") (pin "4") (pinfunction "MNT_3_4") (pintype "passive"))
      (node (ref "J20") (pin "5") (pinfunction "MNT_4_5") (pintype "passive"))
      (node (ref "J21") (pin "2") (pinfunction "MNT_1_2") (pintype "passive"))
      (node (ref "J21") (pin "3") (pinfunction "MNT_2_3") (pintype "passive"))
      (node (ref "J21") (pin "4") (pinfunction "MNT_3_4") (pintype "passive"))
      (node (ref "J21") (pin "5") (pinfunction "MNT_4_5") (pintype "passive"))
      (node (ref "P29") (pin "1") (pinfunction "1_1") (pintype "passive"))
      (node (ref "P29") (pin "30") (pinfunction "30_30") (pintype "passive"))
      (node (ref "P30") (pin "4") (pinfunction "4_4") (pintype "passive"))
      (node (ref "P33") (pin "3") (pinfunction "3_3") (pintype "passive"))
      (node (ref "R75") (pin "1") (pinfunction "1_1") (pintype "passive"))
      (node (ref "U13") (pin "10") (pinfunction "GND_10") (pintype "input"))
      (node (ref "U13") (pin "106") (pinfunction "VSS_106") (pintype "input"))
      (node (ref "U13") (pin "11") (pinfunction "GND_11") (pintype "input"))
      (node (ref "U13") (pin "111") (pinfunction "VSS_111") (pintype "input"))
      (node (ref "U13") (pin "115") (pinfunction "VSS_115") (pintype "input"))
      (node (ref "U13") (pin "116") (pinfunction "VSS_116") (pintype "input"))
      (node (ref "U13") (pin "117") (pinfunction "VSS_117") (pintype "input"))
      (node (ref "U13") (pin "118") (pinfunction "VSS_118") (pintype "input"))
      (node (ref "U13") (pin "119") (pinfunction "VSS_119") (pintype "input"))
      (node (ref "U13") (pin "120") (pinfunction "VSS_120") (pintype "input"))
      (node (ref "U13") (pin "124") (pinfunction "VSS_124") (pintype "input"))
      (node (ref "U13") (pin "125") (pinfunction "VSS_125") (pintype "input"))
      (node (ref "U13") (pin "126") (pinfunction "VSS_126") (pintype "input"))
      (node (ref "U13") (pin "127") (pinfunction "VSS_127") (pintype "input"))
      (node (ref "U13") (pin "128") (pinfunction "VSS_128") (pintype "input"))
      (node (ref "U13") (pin "129") (pinfunction "VSS_129") (pintype "input"))
      (node (ref "U13") (pin "131") (pinfunction "VSS_131") (pintype "input"))
      (node (ref "U13") (pin "140") (pinfunction "VSS_140") (pintype "input"))
      (node (ref "U13") (pin "142") (pinfunction "VSS_142") (pintype "input"))
      (node (ref "U13") (pin "143") (pinfunction "RF_TXGND_143") (pintype "input"))
      (node (ref "U13") (pin "147") (pinfunction "VSS_147") (pintype "input"))
      (node (ref "U13") (pin "160") (pinfunction "VSS_160") (pintype "input"))
      (node (ref "U13") (pin "161") (pinfunction "VSS_161") (pintype "input"))
      (node (ref "U13") (pin "162") (pinfunction "VSS_162") (pintype "input"))
      (node (ref "U13") (pin "163") (pinfunction "VSS_163") (pintype "input"))
      (node (ref "U13") (pin "164") (pinfunction "VSS_164") (pintype "input"))
      (node (ref "U13") (pin "165") (pinfunction "VSS_165") (pintype "input"))
      (node (ref "U13") (pin "169") (pinfunction "VSS_169") (pintype "input"))
      (node (ref "U13") (pin "170") (pinfunction "VSS_170") (pintype "input"))
      (node (ref "U13") (pin "171") (pinfunction "VSS_171") (pintype "input"))
      (node (ref "U13") (pin "172") (pinfunction "VSS_172") (pintype "input"))
      (node (ref "U13") (pin "173") (pinfunction "VSS_173") (pintype "input"))
      (node (ref "U13") (pin "174") (pinfunction "VSS_174") (pintype "input"))
      (node (ref "U13") (pin "178") (pinfunction "VSS_178") (pintype "input"))
      (node (ref "U13") (pin "179") (pinfunction "RF_RXGND_179") (pintype "input"))
      (node (ref "U13") (pin "183") (pinfunction "VSS_183") (pintype "input"))
      (node (ref "U13") (pin "185") (pinfunction "VSS_185") (pintype "input"))
      (node (ref "U13") (pin "194") (pinfunction "VSS_194") (pintype "input"))
      (node (ref "U13") (pin "196") (pinfunction "VSS_196") (pintype "input"))
      (node (ref "U13") (pin "197") (pinfunction "VSS_197") (pintype "input"))
      (node (ref "U13") (pin "198") (pinfunction "VSS_198") (pintype "input"))
      (node (ref "U13") (pin "199") (pinfunction "VSS_199") (pintype "input"))
      (node (ref "U13") (pin "20") (pinfunction "VSS_20") (pintype "input"))
      (node (ref "U13") (pin "200") (pinfunction "VSS_200") (pintype "input"))
      (node (ref "U13") (pin "201") (pinfunction "VSS_201") (pintype "input"))
      (node (ref "U13") (pin "214") (pinfunction "VSS_214") (pintype "input"))
      (node (ref "U13") (pin "219") (pinfunction "VSS_219") (pintype "input"))
      (node (ref "U13") (pin "223") (pinfunction "VSS_223") (pintype "input"))
      (node (ref "U13") (pin "224") (pinfunction "VSS_224") (pintype "input"))
      (node (ref "U13") (pin "225") (pinfunction "VSS_225") (pintype "input"))
      (node (ref "U13") (pin "226") (pinfunction "VSS_226") (pintype "input"))
      (node (ref "U13") (pin "227") (pinfunction "VSS_227") (pintype "input"))
      (node (ref "U13") (pin "228") (pinfunction "VSS_228") (pintype "input"))
      (node (ref "U13") (pin "23") (pinfunction "VSS_23") (pintype "input"))
      (node (ref "U13") (pin "232") (pinfunction "VSS_232") (pintype "input"))
      (node (ref "U13") (pin "233") (pinfunction "VSS_233") (pintype "input"))
      (node (ref "U13") (pin "234") (pinfunction "VSS_234") (pintype "input"))
      (node (ref "U13") (pin "235") (pinfunction "VSS_235") (pintype "input"))
      (node (ref "U13") (pin "236") (pinfunction "VSS_236") (pintype "input"))
      (node (ref "U13") (pin "237") (pinfunction "VSS_237") (pintype "input"))
      (node (ref "U13") (pin "239") (pinfunction "VSS_239") (pintype "input"))
      (node (ref "U13") (pin "248") (pinfunction "VSS_248") (pintype "input"))
      (node (ref "U13") (pin "250") (pinfunction "VSS_250") (pintype "input"))
      (node (ref "U13") (pin "255") (pinfunction "VSS_255") (pintype "input"))
      (node (ref "U13") (pin "259") (pinfunction "VSS_259") (pintype "input"))
      (node (ref "U13") (pin "26") (pinfunction "VSS_26") (pintype "input"))
      (node (ref "U13") (pin "260") (pinfunction "VSS_260") (pintype "input"))
      (node (ref "U13") (pin "261") (pinfunction "VSS_261") (pintype "input"))
      (node (ref "U13") (pin "262") (pinfunction "VSS_262") (pintype "input"))
      (node (ref "U13") (pin "263") (pinfunction "VSS_263") (pintype "input"))
      (node (ref "U13") (pin "264") (pinfunction "VSS_264") (pintype "input"))
      (node (ref "U13") (pin "268") (pinfunction "VSS_268") (pintype "input"))
      (node (ref "U13") (pin "269") (pinfunction "VSS_269") (pintype "input"))
      (node (ref "U13") (pin "270") (pinfunction "VSS_270") (pintype "input"))
      (node (ref "U13") (pin "283") (pinfunction "GND_283") (pintype "input"))
      (node (ref "U13") (pin "29") (pinfunction "VSS_29") (pintype "input"))
      (node (ref "U13") (pin "290") (pinfunction "VSS_290") (pintype "input"))
      (node (ref "U13") (pin "293") (pinfunction "VSS_293") (pintype "input"))
      (node (ref "U13") (pin "296") (pinfunction "VSS_296") (pintype "input"))
      (node (ref "U13") (pin "299") (pinfunction "VSS_299") (pintype "input"))
      (node (ref "U13") (pin "301") (pinfunction "GND_301") (pintype "input"))
      (node (ref "U13") (pin "302") (pinfunction "VSS_302") (pintype "input"))
      (node (ref "U13") (pin "305") (pinfunction "VSS_305") (pintype "input"))
      (node (ref "U13") (pin "319") (pinfunction "GND_319") (pintype "input"))
      (node (ref "U13") (pin "32") (pinfunction "VSS_32") (pintype "input"))
      (node (ref "U13") (pin "35") (pinfunction "VSS_35") (pintype "input"))
      (node (ref "U13") (pin "55") (pinfunction "VSS_55") (pintype "input"))
      (node (ref "U13") (pin "56") (pinfunction "VSS_56") (pintype "input"))
      (node (ref "U13") (pin "57") (pinfunction "VSS_57") (pintype "input"))
      (node (ref "U13") (pin "61") (pinfunction "VSS_61") (pintype "input"))
      (node (ref "U13") (pin "62") (pinfunction "VSS_62") (pintype "input"))
      (node (ref "U13") (pin "63") (pinfunction "VSS_63") (pintype "input"))
      (node (ref "U13") (pin "64") (pinfunction "VSS_64") (pintype "input"))
      (node (ref "U13") (pin "65") (pinfunction "VSS_65") (pintype "input"))
      (node (ref "U13") (pin "66") (pinfunction "VSS_66") (pintype "input"))
      (node (ref "U13") (pin "70") (pinfunction "VSS_70") (pintype "input"))
      (node (ref "U13") (pin "75") (pinfunction "VSS_75") (pintype "input"))
      (node (ref "U13") (pin "77") (pinfunction "VSS_77") (pintype "input"))
      (node (ref "U13") (pin "86") (pinfunction "VSS_86") (pintype "input"))
      (node (ref "U13") (pin "88") (pinfunction "VSS_88") (pintype "input"))
      (node (ref "U13") (pin "89") (pinfunction "VSS_89") (pintype "input"))
      (node (ref "U13") (pin "90") (pinfunction "VSS_90") (pintype "input"))
      (node (ref "U13") (pin "91") (pinfunction "VSS_91") (pintype "input"))
      (node (ref "U13") (pin "92") (pinfunction "VSS_92") (pintype "input"))
      (node (ref "U13") (pin "93") (pinfunction "VSS_93") (pintype "input"))
      (node (ref "Y1") (pin "2") (pinfunction "Gnd_2") (pintype "power_in"))
    )
    (net (code "62") (name "LDO_VDD_ALWAYS_ON") (class "Default")
      (node (ref "U13") (pin "49") (pinfunction "LDO_VDD_AON_49") (pintype "input"))
    )
    (net (code "63") (name "LDO_VDD_A_RF") (class "Default")
      (node (ref "U13") (pin "137") (pinfunction "VDDIO_BD_137") (pintype "input"))
      (node (ref "U13") (pin "138") (pinfunction "VDDIO_BD_138") (pintype "input"))
    )
    (net (code "64") (name "LDO_VDD_D") (class "Default")
      (node (ref "U13") (pin "135") (pinfunction "VDDIO_BDFS_135") (pintype "input"))
      (node (ref "U13") (pin "136") (pinfunction "VDDIO_BDFS_136") (pintype "input"))
      (node (ref "U13") (pin "190") (pinfunction "VDD_BD_190") (pintype "input"))
    )
    (net (code "65") (name "Net-(H1-Pad5)") (class "Default")
      (node (ref "H1") (pin "5") (pinfunction "5_5") (pintype "passive"))
      (node (ref "J20") (pin "1") (pinfunction "1_1") (pintype "passive"))
    )
    (net (code "66") (name "Net-(H2-Pad5)") (class "Default")
      (node (ref "H2") (pin "5") (pinfunction "5_5") (pintype "passive"))
      (node (ref "J21") (pin "1") (pinfunction "1_1") (pintype "passive"))
    )
    (net (code "67") (name "Net-(J14-PadD29)") (class "Default")
      (node (ref "J14") (pin "D29") (pinfunction "D29_D29") (pintype "passive"))
      (node (ref "R70") (pin "1") (pinfunction "1_1") (pintype "passive"))
    )
    (net (code "68") (name "Net-(J14-PadD30)") (class "Default")
      (node (ref "J14") (pin "D30") (pinfunction "D30_D30") (pintype "passive"))
      (node (ref "R69") (pin "1") (pinfunction "1_1") (pintype "passive"))
      (node (ref "R71") (pin "1") (pinfunction "1_1") (pintype "passive"))
    )
    (net (code "69") (name "Net-(J14-PadD31)") (class "Default")
      (node (ref "J14") (pin "D31") (pinfunction "D31_D31") (pintype "passive"))
      (node (ref "R69") (pin "2") (pinfunction "2_2") (pintype "passive"))
      (node (ref "R72") (pin "1") (pinfunction "1_1") (pintype "passive"))
    )
    (net (code "70") (name "Net-(J14-PadD33)") (class "Default")
      (node (ref "J14") (pin "D33") (pinfunction "D33_D33") (pintype "passive"))
      (node (ref "R73") (pin "1") (pinfunction "1_1") (pintype "passive"))
    )
    (net (code "71") (name "Net-(J14-PadD34)") (class "Default")
      (node (ref "J14") (pin "D34") (pinfunction "D34_D34") (pintype "passive"))
      (node (ref "R74") (pin "1") (pinfunction "1_1") (pintype "passive"))
    )
    (net (code "72") (name "Net-(U13A-CLK_BYPASS_0)") (class "Default")
      (node (ref "R82") (pin "2") (pinfunction "2_2") (pintype "passive"))
      (node (ref "U13") (pin "47") (pinfunction "CLK_BYPASS_0_47") (pintype "input"))
    )
    (net (code "73") (name "Net-(U13A-CLK_BYPASS_1)") (class "Default")
      (node (ref "R80") (pin "2") (pinfunction "2_2") (pintype "passive"))
      (node (ref "U13") (pin "46") (pinfunction "CLK_BYPASS_1_46") (pintype "input"))
    )
    (net (code "74") (name "Net-(U13A-TL_CLK)") (class "Default")
      (node (ref "R81") (pin "1") (pinfunction "1_1") (pintype "passive"))
      (node (ref "U13") (pin "277") (pinfunction "TL_CLK_277") (pintype "input"))
    )
    (net (code "75") (name "Net-(U13A-TL_IN_DAT)") (class "Default")
      (node (ref "R78") (pin "1") (pinfunction "1_1") (pintype "passive"))
      (node (ref "U13") (pin "295") (pinfunction "TL_IN_DAT_295") (pintype "input"))
    )
    (net (code "76") (name "Net-(U13A-TL_IN_RDY)") (class "Default")
      (node (ref "R79") (pin "1") (pinfunction "1_1") (pintype "passive"))
      (node (ref "U13") (pin "294") (pinfunction "TL_IN_RDY_294") (pintype "input"))
    )
    (net (code "77") (name "Net-(U13A-TL_IN_VAL)") (class "Default")
      (node (ref "R77") (pin "1") (pinfunction "1_1") (pintype "passive"))
      (node (ref "U13") (pin "311") (pinfunction "TL_IN_VAL_311") (pintype "input"))
    )
    (net (code "78") (name "Net-(U13A-TL_OUT_DAT)") (class "Default")
      (node (ref "R76") (pin "1") (pinfunction "1_1") (pintype "passive"))
      (node (ref "U13") (pin "312") (pinfunction "TL_OUT_DAT_312") (pintype "input"))
    )
    (net (code "79") (name "Net-(U13A-TL_OUT_RDY)") (class "Default")
      (node (ref "R84") (pin "1") (pinfunction "1_1") (pintype "passive"))
      (node (ref "U13") (pin "275") (pinfunction "TL_OUT_RDY_275") (pintype "input"))
    )
    (net (code "80") (name "Net-(U13A-TL_OUT_VAL)") (class "Default")
      (node (ref "R83") (pin "1") (pinfunction "1_1") (pintype "passive"))
      (node (ref "U13") (pin "276") (pinfunction "TL_OUT_VAL_276") (pintype "input"))
    )
    (net (code "81") (name "Net-(Y1-Output)") (class "Default")
      (node (ref "H2") (pin "3") (pinfunction "3_3") (pintype "passive"))
      (node (ref "Y1") (pin "3") (pinfunction "Output_3") (pintype "output"))
    )
    (net (code "82") (name "VDD_1V8") (class "Default")
      (node (ref "C82") (pin "2") (pinfunction "2_2") (pintype "passive"))
      (node (ref "Y1") (pin "1") (pinfunction "Tri-state_1") (pintype "input"))
      (node (ref "Y1") (pin "4") (pinfunction "Vdd_4") (pintype "power_in"))
    )
    (net (code "83") (name "VDD_ALWAYS_ON") (class "Default")
      (node (ref "U13") (pin "189") (pinfunction "VDD_BDFS_189") (pintype "input"))
    )
    (net (code "84") (name "VDD_A_RF") (class "Default")
      (node (ref "U13") (pin "12") (pinfunction "VDD_A_RF_12") (pintype "input"))
      (node (ref "U13") (pin "155") (pinfunction "VDD_LVDS_155") (pintype "input"))
    )
    (net (code "85") (name "VDD_BATT") (class "Default")
      (node (ref "U13") (pin "100") (pinfunction "VDD_100") (pintype "input"))
      (node (ref "U13") (pin "101") (pinfunction "VDD_101") (pintype "input"))
      (node (ref "U13") (pin "102") (pinfunction "VDD_102") (pintype "input"))
      (node (ref "U13") (pin "133") (pinfunction "VDD_133") (pintype "input"))
      (node (ref "U13") (pin "134") (pinfunction "VDD_134") (pintype "input"))
      (node (ref "U13") (pin "151") (pinfunction "VDD_151") (pintype "input"))
      (node (ref "U13") (pin "153") (pinfunction "VDD_153") (pintype "input"))
      (node (ref "U13") (pin "154") (pinfunction "VDD_154") (pintype "input"))
      (node (ref "U13") (pin "156") (pinfunction "VDD_156") (pintype "input"))
      (node (ref "U13") (pin "187") (pinfunction "VDD_187") (pintype "input"))
      (node (ref "U13") (pin "192") (pinfunction "VDD_192") (pintype "input"))
      (node (ref "U13") (pin "205") (pinfunction "VDD_205") (pintype "input"))
      (node (ref "U13") (pin "206") (pinfunction "VDD_206") (pintype "input"))
      (node (ref "U13") (pin "209") (pinfunction "VDD_209") (pintype "input"))
      (node (ref "U13") (pin "210") (pinfunction "VDD_210") (pintype "input"))
      (node (ref "U13") (pin "241") (pinfunction "VDD_241") (pintype "input"))
      (node (ref "U13") (pin "242") (pinfunction "VDD_242") (pintype "input"))
      (node (ref "U13") (pin "243") (pinfunction "VDD_243") (pintype "input"))
      (node (ref "U13") (pin "244") (pinfunction "VDD_244") (pintype "input"))
      (node (ref "U13") (pin "245") (pinfunction "VDD_245") (pintype "input"))
      (node (ref "U13") (pin "246") (pinfunction "VDD_246") (pintype "input"))
      (node (ref "U13") (pin "79") (pinfunction "VDD_79") (pintype "input"))
      (node (ref "U13") (pin "80") (pinfunction "VDD_80") (pintype "input"))
      (node (ref "U13") (pin "81") (pinfunction "VDD_81") (pintype "input"))
      (node (ref "U13") (pin "82") (pinfunction "VDD_82") (pintype "input"))
      (node (ref "U13") (pin "83") (pinfunction "VDD_83") (pintype "input"))
      (node (ref "U13") (pin "84") (pinfunction "VDD_84") (pintype "input"))
      (node (ref "U13") (pin "97") (pinfunction "VDD_97") (pintype "input"))
      (node (ref "U13") (pin "98") (pinfunction "VDD_98") (pintype "input"))
      (node (ref "U13") (pin "99") (pinfunction "VDD_99") (pintype "input"))
    )
    (net (code "86") (name "VDD_D") (class "Default")
      (node (ref "U13") (pin "152") (pinfunction "VDDIO_152") (pintype "input"))
    )
    (net (code "87") (name "VDD_IO") (class "Default")
      (node (ref "*2") (pin "1") (pinfunction "+_1") (pintype "passive"))
      (node (ref "P33") (pin "1") (pinfunction "1_1") (pintype "passive"))
      (node (ref "U13") (pin "191") (pinfunction "VDDIO_LVDS_191") (pintype "input"))
      (node (ref "U13") (pin "45") (pinfunction "VDD_IO_45") (pintype "input"))
      (node (ref "U13") (pin "7") (pinfunction "VDD_IO_7") (pintype "input"))
      (node (ref "U13") (pin "9") (pinfunction "VDD_IO_9") (pintype "input"))
    )
    (net (code "88") (name "unconnected-(*2-DIn-Pad6)") (class "Default")
      (node (ref "*2") (pin "6") (pinfunction "DIn_6") (pintype "passive+no_connect"))
    )
    (net (code "89") (name "unconnected-(*2-DOut-Pad4)") (class "Default")
      (node (ref "*2") (pin "4") (pinfunction "DOut_4") (pintype "passive+no_connect"))
    )
    (net (code "90") (name "unconnected-(*2-GND-Pad5)") (class "Default")
      (node (ref "*2") (pin "5") (pinfunction "GND_5") (pintype "passive+no_connect"))
    )
    (net (code "91") (name "unconnected-(*2-VDD-Pad3)") (class "Default")
      (node (ref "*2") (pin "3") (pinfunction "VDD_3") (pintype "passive+no_connect"))
    )
    (net (code "92") (name "unconnected-(H1-Pad3)") (class "Default")
      (node (ref "H1") (pin "3") (pinfunction "3_3") (pintype "passive+no_connect"))
    )
    (net (code "93") (name "unconnected-(J14-PadA2)") (class "Default")
      (node (ref "J14") (pin "A2") (pinfunction "A2_A2") (pintype "passive+no_connect"))
    )
    (net (code "94") (name "unconnected-(J14-PadA3)") (class "Default")
      (node (ref "J14") (pin "A3") (pinfunction "A3_A3") (pintype "passive+no_connect"))
    )
    (net (code "95") (name "unconnected-(J14-PadA6)") (class "Default")
      (node (ref "J14") (pin "A6") (pinfunction "A6_A6") (pintype "passive+no_connect"))
    )
    (net (code "96") (name "unconnected-(J14-PadA7)") (class "Default")
      (node (ref "J14") (pin "A7") (pinfunction "A7_A7") (pintype "passive+no_connect"))
    )
    (net (code "97") (name "unconnected-(J14-PadA10)") (class "Default")
      (node (ref "J14") (pin "A10") (pinfunction "A10_A10") (pintype "passive+no_connect"))
    )
    (net (code "98") (name "unconnected-(J14-PadA11)") (class "Default")
      (node (ref "J14") (pin "A11") (pinfunction "A11_A11") (pintype "passive+no_connect"))
    )
    (net (code "99") (name "unconnected-(J14-PadA14)") (class "Default")
      (node (ref "J14") (pin "A14") (pinfunction "A14_A14") (pintype "passive+no_connect"))
    )
    (net (code "100") (name "unconnected-(J14-PadA15)") (class "Default")
      (node (ref "J14") (pin "A15") (pinfunction "A15_A15") (pintype "passive+no_connect"))
    )
    (net (code "101") (name "unconnected-(J14-PadA18)") (class "Default")
      (node (ref "J14") (pin "A18") (pinfunction "A18_A18") (pintype "passive+no_connect"))
    )
    (net (code "102") (name "unconnected-(J14-PadA19)") (class "Default")
      (node (ref "J14") (pin "A19") (pinfunction "A19_A19") (pintype "passive+no_connect"))
    )
    (net (code "103") (name "unconnected-(J14-PadA22)") (class "Default")
      (node (ref "J14") (pin "A22") (pinfunction "A22_A22") (pintype "passive+no_connect"))
    )
    (net (code "104") (name "unconnected-(J14-PadA23)") (class "Default")
      (node (ref "J14") (pin "A23") (pinfunction "A23_A23") (pintype "passive+no_connect"))
    )
    (net (code "105") (name "unconnected-(J14-PadA26)") (class "Default")
      (node (ref "J14") (pin "A26") (pinfunction "A26_A26") (pintype "passive+no_connect"))
    )
    (net (code "106") (name "unconnected-(J14-PadA27)") (class "Default")
      (node (ref "J14") (pin "A27") (pinfunction "A27_A27") (pintype "passive+no_connect"))
    )
    (net (code "107") (name "unconnected-(J14-PadA30)") (class "Default")
      (node (ref "J14") (pin "A30") (pinfunction "A30_A30") (pintype "passive+no_connect"))
    )
    (net (code "108") (name "unconnected-(J14-PadA31)") (class "Default")
      (node (ref "J14") (pin "A31") (pinfunction "A31_A31") (pintype "passive+no_connect"))
    )
    (net (code "109") (name "unconnected-(J14-PadA34)") (class "Default")
      (node (ref "J14") (pin "A34") (pinfunction "A34_A34") (pintype "passive+no_connect"))
    )
    (net (code "110") (name "unconnected-(J14-PadA35)") (class "Default")
      (node (ref "J14") (pin "A35") (pinfunction "A35_A35") (pintype "passive+no_connect"))
    )
    (net (code "111") (name "unconnected-(J14-PadA38)") (class "Default")
      (node (ref "J14") (pin "A38") (pinfunction "A38_A38") (pintype "passive+no_connect"))
    )
    (net (code "112") (name "unconnected-(J14-PadA39)") (class "Default")
      (node (ref "J14") (pin "A39") (pinfunction "A39_A39") (pintype "passive+no_connect"))
    )
    (net (code "113") (name "unconnected-(J14-PadB1)") (class "Default")
      (node (ref "J14") (pin "B1") (pinfunction "B1_B1") (pintype "passive+no_connect"))
    )
    (net (code "114") (name "unconnected-(J14-PadB4)") (class "Default")
      (node (ref "J14") (pin "B4") (pinfunction "B4_B4") (pintype "passive+no_connect"))
    )
    (net (code "115") (name "unconnected-(J14-PadB5)") (class "Default")
      (node (ref "J14") (pin "B5") (pinfunction "B5_B5") (pintype "passive+no_connect"))
    )
    (net (code "116") (name "unconnected-(J14-PadB8)") (class "Default")
      (node (ref "J14") (pin "B8") (pinfunction "B8_B8") (pintype "passive+no_connect"))
    )
    (net (code "117") (name "unconnected-(J14-PadB9)") (class "Default")
      (node (ref "J14") (pin "B9") (pinfunction "B9_B9") (pintype "passive+no_connect"))
    )
    (net (code "118") (name "unconnected-(J14-PadB12)") (class "Default")
      (node (ref "J14") (pin "B12") (pinfunction "B12_B12") (pintype "passive+no_connect"))
    )
    (net (code "119") (name "unconnected-(J14-PadB13)") (class "Default")
      (node (ref "J14") (pin "B13") (pinfunction "B13_B13") (pintype "passive+no_connect"))
    )
    (net (code "120") (name "unconnected-(J14-PadB16)") (class "Default")
      (node (ref "J14") (pin "B16") (pinfunction "B16_B16") (pintype "passive+no_connect"))
    )
    (net (code "121") (name "unconnected-(J14-PadB17)") (class "Default")
      (node (ref "J14") (pin "B17") (pinfunction "B17_B17") (pintype "passive+no_connect"))
    )
    (net (code "122") (name "unconnected-(J14-PadB20)") (class "Default")
      (node (ref "J14") (pin "B20") (pinfunction "B20_B20") (pintype "passive+no_connect"))
    )
    (net (code "123") (name "unconnected-(J14-PadB21)") (class "Default")
      (node (ref "J14") (pin "B21") (pinfunction "B21_B21") (pintype "passive+no_connect"))
    )
    (net (code "124") (name "unconnected-(J14-PadB24)") (class "Default")
      (node (ref "J14") (pin "B24") (pinfunction "B24_B24") (pintype "passive+no_connect"))
    )
    (net (code "125") (name "unconnected-(J14-PadB25)") (class "Default")
      (node (ref "J14") (pin "B25") (pinfunction "B25_B25") (pintype "passive+no_connect"))
    )
    (net (code "126") (name "unconnected-(J14-PadB28)") (class "Default")
      (node (ref "J14") (pin "B28") (pinfunction "B28_B28") (pintype "passive+no_connect"))
    )
    (net (code "127") (name "unconnected-(J14-PadB29)") (class "Default")
      (node (ref "J14") (pin "B29") (pinfunction "B29_B29") (pintype "passive+no_connect"))
    )
    (net (code "128") (name "unconnected-(J14-PadB32)") (class "Default")
      (node (ref "J14") (pin "B32") (pinfunction "B32_B32") (pintype "passive+no_connect"))
    )
    (net (code "129") (name "unconnected-(J14-PadB33)") (class "Default")
      (node (ref "J14") (pin "B33") (pinfunction "B33_B33") (pintype "passive+no_connect"))
    )
    (net (code "130") (name "unconnected-(J14-PadB36)") (class "Default")
      (node (ref "J14") (pin "B36") (pinfunction "B36_B36") (pintype "passive+no_connect"))
    )
    (net (code "131") (name "unconnected-(J14-PadB37)") (class "Default")
      (node (ref "J14") (pin "B37") (pinfunction "B37_B37") (pintype "passive+no_connect"))
    )
    (net (code "132") (name "unconnected-(J14-PadB40)") (class "Default")
      (node (ref "J14") (pin "B40") (pinfunction "B40_B40") (pintype "passive+no_connect"))
    )
    (net (code "133") (name "unconnected-(J14-PadC2)") (class "Default")
      (node (ref "J14") (pin "C2") (pinfunction "C2_C2") (pintype "passive+no_connect"))
    )
    (net (code "134") (name "unconnected-(J14-PadC3)") (class "Default")
      (node (ref "J14") (pin "C3") (pinfunction "C3_C3") (pintype "passive+no_connect"))
    )
    (net (code "135") (name "unconnected-(J14-PadC6)") (class "Default")
      (node (ref "J14") (pin "C6") (pinfunction "C6_C6") (pintype "passive+no_connect"))
    )
    (net (code "136") (name "unconnected-(J14-PadC7)") (class "Default")
      (node (ref "J14") (pin "C7") (pinfunction "C7_C7") (pintype "passive+no_connect"))
    )
    (net (code "137") (name "unconnected-(J14-PadC10)") (class "Default")
      (node (ref "J14") (pin "C10") (pinfunction "C10_C10") (pintype "passive+no_connect"))
    )
    (net (code "138") (name "unconnected-(J14-PadC11)") (class "Default")
      (node (ref "J14") (pin "C11") (pinfunction "C11_C11") (pintype "passive+no_connect"))
    )
    (net (code "139") (name "unconnected-(J14-PadC14)") (class "Default")
      (node (ref "J14") (pin "C14") (pinfunction "C14_C14") (pintype "passive+no_connect"))
    )
    (net (code "140") (name "unconnected-(J14-PadC15)") (class "Default")
      (node (ref "J14") (pin "C15") (pinfunction "C15_C15") (pintype "passive+no_connect"))
    )
    (net (code "141") (name "unconnected-(J14-PadC18)") (class "Default")
      (node (ref "J14") (pin "C18") (pinfunction "C18_C18") (pintype "passive+no_connect"))
    )
    (net (code "142") (name "unconnected-(J14-PadC19)") (class "Default")
      (node (ref "J14") (pin "C19") (pinfunction "C19_C19") (pintype "passive+no_connect"))
    )
    (net (code "143") (name "unconnected-(J14-PadC22)") (class "Default")
      (node (ref "J14") (pin "C22") (pinfunction "C22_C22") (pintype "passive+no_connect"))
    )
    (net (code "144") (name "unconnected-(J14-PadC23)") (class "Default")
      (node (ref "J14") (pin "C23") (pinfunction "C23_C23") (pintype "passive+no_connect"))
    )
    (net (code "145") (name "unconnected-(J14-PadC26)") (class "Default")
      (node (ref "J14") (pin "C26") (pinfunction "C26_C26") (pintype "passive+no_connect"))
    )
    (net (code "146") (name "unconnected-(J14-PadC27)") (class "Default")
      (node (ref "J14") (pin "C27") (pinfunction "C27_C27") (pintype "passive+no_connect"))
    )
    (net (code "147") (name "unconnected-(J14-PadC34)") (class "Default")
      (node (ref "J14") (pin "C34") (pinfunction "C34_C34") (pintype "passive+no_connect"))
    )
    (net (code "148") (name "unconnected-(J14-PadC35)") (class "Default")
      (node (ref "J14") (pin "C35") (pinfunction "C35_C35") (pintype "passive+no_connect"))
    )
    (net (code "149") (name "unconnected-(J14-PadC37)") (class "Default")
      (node (ref "J14") (pin "C37") (pinfunction "C37_C37") (pintype "passive+no_connect"))
    )
    (net (code "150") (name "unconnected-(J14-PadC39)") (class "Default")
      (node (ref "J14") (pin "C39") (pinfunction "C39_C39") (pintype "passive+no_connect"))
    )
    (net (code "151") (name "unconnected-(J14-PadD1)") (class "Default")
      (node (ref "J14") (pin "D1") (pinfunction "D1_D1") (pintype "passive+no_connect"))
    )
    (net (code "152") (name "unconnected-(J14-PadD4)") (class "Default")
      (node (ref "J14") (pin "D4") (pinfunction "D4_D4") (pintype "passive+no_connect"))
    )
    (net (code "153") (name "unconnected-(J14-PadD5)") (class "Default")
      (node (ref "J14") (pin "D5") (pinfunction "D5_D5") (pintype "passive+no_connect"))
    )
    (net (code "154") (name "unconnected-(J14-PadD8)") (class "Default")
      (node (ref "J14") (pin "D8") (pinfunction "D8_D8") (pintype "passive+no_connect"))
    )
    (net (code "155") (name "unconnected-(J14-PadD9)") (class "Default")
      (node (ref "J14") (pin "D9") (pinfunction "D9_D9") (pintype "passive+no_connect"))
    )
    (net (code "156") (name "unconnected-(J14-PadD11)") (class "Default")
      (node (ref "J14") (pin "D11") (pinfunction "D11_D11") (pintype "passive+no_connect"))
    )
    (net (code "157") (name "unconnected-(J14-PadD12)") (class "Default")
      (node (ref "J14") (pin "D12") (pinfunction "D12_D12") (pintype "passive+no_connect"))
    )
    (net (code "158") (name "unconnected-(J14-PadD14)") (class "Default")
      (node (ref "J14") (pin "D14") (pinfunction "D14_D14") (pintype "passive+no_connect"))
    )
    (net (code "159") (name "unconnected-(J14-PadD15)") (class "Default")
      (node (ref "J14") (pin "D15") (pinfunction "D15_D15") (pintype "passive+no_connect"))
    )
    (net (code "160") (name "unconnected-(J14-PadD17)") (class "Default")
      (node (ref "J14") (pin "D17") (pinfunction "D17_D17") (pintype "passive+no_connect"))
    )
    (net (code "161") (name "unconnected-(J14-PadD18)") (class "Default")
      (node (ref "J14") (pin "D18") (pinfunction "D18_D18") (pintype "passive+no_connect"))
    )
    (net (code "162") (name "unconnected-(J14-PadD20)") (class "Default")
      (node (ref "J14") (pin "D20") (pinfunction "D20_D20") (pintype "passive+no_connect"))
    )
    (net (code "163") (name "unconnected-(J14-PadD21)") (class "Default")
      (node (ref "J14") (pin "D21") (pinfunction "D21_D21") (pintype "passive+no_connect"))
    )
    (net (code "164") (name "unconnected-(J14-PadD23)") (class "Default")
      (node (ref "J14") (pin "D23") (pinfunction "D23_D23") (pintype "passive+no_connect"))
    )
    (net (code "165") (name "unconnected-(J14-PadD24)") (class "Default")
      (node (ref "J14") (pin "D24") (pinfunction "D24_D24") (pintype "passive+no_connect"))
    )
    (net (code "166") (name "unconnected-(J14-PadD26)") (class "Default")
      (node (ref "J14") (pin "D26") (pinfunction "D26_D26") (pintype "passive+no_connect"))
    )
    (net (code "167") (name "unconnected-(J14-PadD27)") (class "Default")
      (node (ref "J14") (pin "D27") (pinfunction "D27_D27") (pintype "passive+no_connect"))
    )
    (net (code "168") (name "unconnected-(J14-PadD32)") (class "Default")
      (node (ref "J14") (pin "D32") (pinfunction "D32_D32") (pintype "passive+no_connect"))
    )
    (net (code "169") (name "unconnected-(J14-PadD35)") (class "Default")
      (node (ref "J14") (pin "D35") (pinfunction "D35_D35") (pintype "passive+no_connect"))
    )
    (net (code "170") (name "unconnected-(J14-PadE2)") (class "Default")
      (node (ref "J14") (pin "E2") (pinfunction "E2_E2") (pintype "passive+no_connect"))
    )
    (net (code "171") (name "unconnected-(J14-PadE3)") (class "Default")
      (node (ref "J14") (pin "E3") (pinfunction "E3_E3") (pintype "passive+no_connect"))
    )
    (net (code "172") (name "unconnected-(J14-PadE12)") (class "Default")
      (node (ref "J14") (pin "E12") (pinfunction "E12_E12") (pintype "passive+no_connect"))
    )
    (net (code "173") (name "unconnected-(J14-PadE15)") (class "Default")
      (node (ref "J14") (pin "E15") (pinfunction "E15_E15") (pintype "passive+no_connect"))
    )
    (net (code "174") (name "unconnected-(J14-PadE16)") (class "Default")
      (node (ref "J14") (pin "E16") (pinfunction "E16_E16") (pintype "passive+no_connect"))
    )
    (net (code "175") (name "unconnected-(J14-PadE18)") (class "Default")
      (node (ref "J14") (pin "E18") (pinfunction "E18_E18") (pintype "passive+no_connect"))
    )
    (net (code "176") (name "unconnected-(J14-PadE19)") (class "Default")
      (node (ref "J14") (pin "E19") (pinfunction "E19_E19") (pintype "passive+no_connect"))
    )
    (net (code "177") (name "unconnected-(J14-PadE21)") (class "Default")
      (node (ref "J14") (pin "E21") (pinfunction "E21_E21") (pintype "passive+no_connect"))
    )
    (net (code "178") (name "unconnected-(J14-PadE22)") (class "Default")
      (node (ref "J14") (pin "E22") (pinfunction "E22_E22") (pintype "passive+no_connect"))
    )
    (net (code "179") (name "unconnected-(J14-PadE24)") (class "Default")
      (node (ref "J14") (pin "E24") (pinfunction "E24_E24") (pintype "passive+no_connect"))
    )
    (net (code "180") (name "unconnected-(J14-PadE25)") (class "Default")
      (node (ref "J14") (pin "E25") (pinfunction "E25_E25") (pintype "passive+no_connect"))
    )
    (net (code "181") (name "unconnected-(J14-PadE27)") (class "Default")
      (node (ref "J14") (pin "E27") (pinfunction "E27_E27") (pintype "passive+no_connect"))
    )
    (net (code "182") (name "unconnected-(J14-PadE28)") (class "Default")
      (node (ref "J14") (pin "E28") (pinfunction "E28_E28") (pintype "passive+no_connect"))
    )
    (net (code "183") (name "unconnected-(J14-PadE31)") (class "Default")
      (node (ref "J14") (pin "E31") (pinfunction "E31_E31") (pintype "passive+no_connect"))
    )
    (net (code "184") (name "unconnected-(J14-PadE36)") (class "Default")
      (node (ref "J14") (pin "E36") (pinfunction "E36_E36") (pintype "passive+no_connect"))
    )
    (net (code "185") (name "unconnected-(J14-PadE37)") (class "Default")
      (node (ref "J14") (pin "E37") (pinfunction "E37_E37") (pintype "passive+no_connect"))
    )
    (net (code "186") (name "unconnected-(J14-PadF1)") (class "Default")
      (node (ref "J14") (pin "F1") (pinfunction "F1_F1") (pintype "passive+no_connect"))
    )
    (net (code "187") (name "unconnected-(J14-PadF5)") (class "Default")
      (node (ref "J14") (pin "F5") (pinfunction "F5_F5") (pintype "passive+no_connect"))
    )
    (net (code "188") (name "unconnected-(J14-PadF7)") (class "Default")
      (node (ref "J14") (pin "F7") (pinfunction "F7_F7") (pintype "passive+no_connect"))
    )
    (net (code "189") (name "unconnected-(J14-PadF8)") (class "Default")
      (node (ref "J14") (pin "F8") (pinfunction "F8_F8") (pintype "passive+no_connect"))
    )
    (net (code "190") (name "unconnected-(J14-PadF10)") (class "Default")
      (node (ref "J14") (pin "F10") (pinfunction "F10_F10") (pintype "passive+no_connect"))
    )
    (net (code "191") (name "unconnected-(J14-PadF11)") (class "Default")
      (node (ref "J14") (pin "F11") (pinfunction "F11_F11") (pintype "passive+no_connect"))
    )
    (net (code "192") (name "unconnected-(J14-PadF13)") (class "Default")
      (node (ref "J14") (pin "F13") (pinfunction "F13_F13") (pintype "passive+no_connect"))
    )
    (net (code "193") (name "unconnected-(J14-PadF14)") (class "Default")
      (node (ref "J14") (pin "F14") (pinfunction "F14_F14") (pintype "passive+no_connect"))
    )
    (net (code "194") (name "unconnected-(J14-PadF16)") (class "Default")
      (node (ref "J14") (pin "F16") (pinfunction "F16_F16") (pintype "passive+no_connect"))
    )
    (net (code "195") (name "unconnected-(J14-PadF17)") (class "Default")
      (node (ref "J14") (pin "F17") (pinfunction "F17_F17") (pintype "passive+no_connect"))
    )
    (net (code "196") (name "unconnected-(J14-PadF19)") (class "Default")
      (node (ref "J14") (pin "F19") (pinfunction "F19_F19") (pintype "passive+no_connect"))
    )
    (net (code "197") (name "unconnected-(J14-PadF20)") (class "Default")
      (node (ref "J14") (pin "F20") (pinfunction "F20_F20") (pintype "passive+no_connect"))
    )
    (net (code "198") (name "unconnected-(J14-PadF22)") (class "Default")
      (node (ref "J14") (pin "F22") (pinfunction "F22_F22") (pintype "passive+no_connect"))
    )
    (net (code "199") (name "unconnected-(J14-PadF23)") (class "Default")
      (node (ref "J14") (pin "F23") (pinfunction "F23_F23") (pintype "passive+no_connect"))
    )
    (net (code "200") (name "unconnected-(J14-PadF25)") (class "Default")
      (node (ref "J14") (pin "F25") (pinfunction "F25_F25") (pintype "passive+no_connect"))
    )
    (net (code "201") (name "unconnected-(J14-PadF26)") (class "Default")
      (node (ref "J14") (pin "F26") (pinfunction "F26_F26") (pintype "passive+no_connect"))
    )
    (net (code "202") (name "unconnected-(J14-PadF28)") (class "Default")
      (node (ref "J14") (pin "F28") (pinfunction "F28_F28") (pintype "passive+no_connect"))
    )
    (net (code "203") (name "unconnected-(J14-PadF29)") (class "Default")
      (node (ref "J14") (pin "F29") (pinfunction "F29_F29") (pintype "passive+no_connect"))
    )
    (net (code "204") (name "unconnected-(J14-PadF31)") (class "Default")
      (node (ref "J14") (pin "F31") (pinfunction "F31_F31") (pintype "passive+no_connect"))
    )
    (net (code "205") (name "unconnected-(J14-PadF32)") (class "Default")
      (node (ref "J14") (pin "F32") (pinfunction "F32_F32") (pintype "passive+no_connect"))
    )
    (net (code "206") (name "unconnected-(J14-PadF34)") (class "Default")
      (node (ref "J14") (pin "F34") (pinfunction "F34_F34") (pintype "passive+no_connect"))
    )
    (net (code "207") (name "unconnected-(J14-PadF35)") (class "Default")
      (node (ref "J14") (pin "F35") (pinfunction "F35_F35") (pintype "passive+no_connect"))
    )
    (net (code "208") (name "unconnected-(J14-PadF37)") (class "Default")
      (node (ref "J14") (pin "F37") (pinfunction "F37_F37") (pintype "passive+no_connect"))
    )
    (net (code "209") (name "unconnected-(J14-PadF38)") (class "Default")
      (node (ref "J14") (pin "F38") (pinfunction "F38_F38") (pintype "passive+no_connect"))
    )
    (net (code "210") (name "unconnected-(J14-PadG22)") (class "Default")
      (node (ref "J14") (pin "G22") (pinfunction "G22_G22") (pintype "passive+no_connect"))
    )
    (net (code "211") (name "unconnected-(J14-PadG24)") (class "Default")
      (node (ref "J14") (pin "G24") (pinfunction "G24_G24") (pintype "passive+no_connect"))
    )
    (net (code "212") (name "unconnected-(J14-PadG25)") (class "Default")
      (node (ref "J14") (pin "G25") (pinfunction "G25_G25") (pintype "passive+no_connect"))
    )
    (net (code "213") (name "unconnected-(J14-PadG27)") (class "Default")
      (node (ref "J14") (pin "G27") (pinfunction "G27_G27") (pintype "passive+no_connect"))
    )
    (net (code "214") (name "unconnected-(J14-PadG28)") (class "Default")
      (node (ref "J14") (pin "G28") (pinfunction "G28_G28") (pintype "passive+no_connect"))
    )
    (net (code "215") (name "unconnected-(J14-PadG30)") (class "Default")
      (node (ref "J14") (pin "G30") (pinfunction "G30_G30") (pintype "passive+no_connect"))
    )
    (net (code "216") (name "unconnected-(J14-PadG31)") (class "Default")
      (node (ref "J14") (pin "G31") (pinfunction "G31_G31") (pintype "passive+no_connect"))
    )
    (net (code "217") (name "unconnected-(J14-PadG33)") (class "Default")
      (node (ref "J14") (pin "G33") (pinfunction "G33_G33") (pintype "passive+no_connect"))
    )
    (net (code "218") (name "unconnected-(J14-PadG34)") (class "Default")
      (node (ref "J14") (pin "G34") (pinfunction "G34_G34") (pintype "passive+no_connect"))
    )
    (net (code "219") (name "unconnected-(J14-PadG36)") (class "Default")
      (node (ref "J14") (pin "G36") (pinfunction "G36_G36") (pintype "passive+no_connect"))
    )
    (net (code "220") (name "unconnected-(J14-PadG37)") (class "Default")
      (node (ref "J14") (pin "G37") (pinfunction "G37_G37") (pintype "passive+no_connect"))
    )
    (net (code "221") (name "unconnected-(J14-PadH1)") (class "Default")
      (node (ref "J14") (pin "H1") (pinfunction "H1_H1") (pintype "passive+no_connect"))
    )
    (net (code "222") (name "unconnected-(J14-PadH2)") (class "Default")
      (node (ref "J14") (pin "H2") (pinfunction "H2_H2") (pintype "passive+no_connect"))
    )
    (net (code "223") (name "unconnected-(J14-PadH22)") (class "Default")
      (node (ref "J14") (pin "H22") (pinfunction "H22_H22") (pintype "passive+no_connect"))
    )
    (net (code "224") (name "unconnected-(J14-PadH23)") (class "Default")
      (node (ref "J14") (pin "H23") (pinfunction "H23_H23") (pintype "passive+no_connect"))
    )
    (net (code "225") (name "unconnected-(J14-PadH25)") (class "Default")
      (node (ref "J14") (pin "H25") (pinfunction "H25_H25") (pintype "passive+no_connect"))
    )
    (net (code "226") (name "unconnected-(J14-PadH26)") (class "Default")
      (node (ref "J14") (pin "H26") (pinfunction "H26_H26") (pintype "passive+no_connect"))
    )
    (net (code "227") (name "unconnected-(J14-PadH28)") (class "Default")
      (node (ref "J14") (pin "H28") (pinfunction "H28_H28") (pintype "passive+no_connect"))
    )
    (net (code "228") (name "unconnected-(J14-PadH29)") (class "Default")
      (node (ref "J14") (pin "H29") (pinfunction "H29_H29") (pintype "passive+no_connect"))
    )
    (net (code "229") (name "unconnected-(J14-PadH31)") (class "Default")
      (node (ref "J14") (pin "H31") (pinfunction "H31_H31") (pintype "passive+no_connect"))
    )
    (net (code "230") (name "unconnected-(J14-PadH32)") (class "Default")
      (node (ref "J14") (pin "H32") (pinfunction "H32_H32") (pintype "passive+no_connect"))
    )
    (net (code "231") (name "unconnected-(J14-PadH34)") (class "Default")
      (node (ref "J14") (pin "H34") (pinfunction "H34_H34") (pintype "passive+no_connect"))
    )
    (net (code "232") (name "unconnected-(J14-PadH35)") (class "Default")
      (node (ref "J14") (pin "H35") (pinfunction "H35_H35") (pintype "passive+no_connect"))
    )
    (net (code "233") (name "unconnected-(J14-PadH37)") (class "Default")
      (node (ref "J14") (pin "H37") (pinfunction "H37_H37") (pintype "passive+no_connect"))
    )
    (net (code "234") (name "unconnected-(J14-PadH38)") (class "Default")
      (node (ref "J14") (pin "H38") (pinfunction "H38_H38") (pintype "passive+no_connect"))
    )
    (net (code "235") (name "unconnected-(J14-PadJ6)") (class "Default")
      (node (ref "J14") (pin "J6") (pinfunction "J6_J6") (pintype "passive+no_connect"))
    )
    (net (code "236") (name "unconnected-(J14-PadJ7)") (class "Default")
      (node (ref "J14") (pin "J7") (pinfunction "J7_J7") (pintype "passive+no_connect"))
    )
    (net (code "237") (name "unconnected-(J14-PadJ9)") (class "Default")
      (node (ref "J14") (pin "J9") (pinfunction "J9_J9") (pintype "passive+no_connect"))
    )
    (net (code "238") (name "unconnected-(J14-PadJ10)") (class "Default")
      (node (ref "J14") (pin "J10") (pinfunction "J10_J10") (pintype "passive+no_connect"))
    )
    (net (code "239") (name "unconnected-(J14-PadJ12)") (class "Default")
      (node (ref "J14") (pin "J12") (pinfunction "J12_J12") (pintype "passive+no_connect"))
    )
    (net (code "240") (name "unconnected-(J14-PadJ13)") (class "Default")
      (node (ref "J14") (pin "J13") (pinfunction "J13_J13") (pintype "passive+no_connect"))
    )
    (net (code "241") (name "unconnected-(J14-PadJ15)") (class "Default")
      (node (ref "J14") (pin "J15") (pinfunction "J15_J15") (pintype "passive+no_connect"))
    )
    (net (code "242") (name "unconnected-(J14-PadJ16)") (class "Default")
      (node (ref "J14") (pin "J16") (pinfunction "J16_J16") (pintype "passive+no_connect"))
    )
    (net (code "243") (name "unconnected-(J14-PadJ18)") (class "Default")
      (node (ref "J14") (pin "J18") (pinfunction "J18_J18") (pintype "passive+no_connect"))
    )
    (net (code "244") (name "unconnected-(J14-PadJ19)") (class "Default")
      (node (ref "J14") (pin "J19") (pinfunction "J19_J19") (pintype "passive+no_connect"))
    )
    (net (code "245") (name "unconnected-(J14-PadJ21)") (class "Default")
      (node (ref "J14") (pin "J21") (pinfunction "J21_J21") (pintype "passive+no_connect"))
    )
    (net (code "246") (name "unconnected-(J14-PadJ22)") (class "Default")
      (node (ref "J14") (pin "J22") (pinfunction "J22_J22") (pintype "passive+no_connect"))
    )
    (net (code "247") (name "unconnected-(J14-PadJ24)") (class "Default")
      (node (ref "J14") (pin "J24") (pinfunction "J24_J24") (pintype "passive+no_connect"))
    )
    (net (code "248") (name "unconnected-(J14-PadJ25)") (class "Default")
      (node (ref "J14") (pin "J25") (pinfunction "J25_J25") (pintype "passive+no_connect"))
    )
    (net (code "249") (name "unconnected-(J14-PadJ27)") (class "Default")
      (node (ref "J14") (pin "J27") (pinfunction "J27_J27") (pintype "passive+no_connect"))
    )
    (net (code "250") (name "unconnected-(J14-PadJ28)") (class "Default")
      (node (ref "J14") (pin "J28") (pinfunction "J28_J28") (pintype "passive+no_connect"))
    )
    (net (code "251") (name "unconnected-(J14-PadJ30)") (class "Default")
      (node (ref "J14") (pin "J30") (pinfunction "J30_J30") (pintype "passive+no_connect"))
    )
    (net (code "252") (name "unconnected-(J14-PadJ31)") (class "Default")
      (node (ref "J14") (pin "J31") (pinfunction "J31_J31") (pintype "passive+no_connect"))
    )
    (net (code "253") (name "unconnected-(J14-PadJ33)") (class "Default")
      (node (ref "J14") (pin "J33") (pinfunction "J33_J33") (pintype "passive+no_connect"))
    )
    (net (code "254") (name "unconnected-(J14-PadJ34)") (class "Default")
      (node (ref "J14") (pin "J34") (pinfunction "J34_J34") (pintype "passive+no_connect"))
    )
    (net (code "255") (name "unconnected-(J14-PadJ36)") (class "Default")
      (node (ref "J14") (pin "J36") (pinfunction "J36_J36") (pintype "passive+no_connect"))
    )
    (net (code "256") (name "unconnected-(J14-PadJ37)") (class "Default")
      (node (ref "J14") (pin "J37") (pinfunction "J37_J37") (pintype "passive+no_connect"))
    )
    (net (code "257") (name "unconnected-(J14-PadJ39)") (class "Default")
      (node (ref "J14") (pin "J39") (pinfunction "J39_J39") (pintype "passive+no_connect"))
    )
    (net (code "258") (name "unconnected-(J14-PadK1)") (class "Default")
      (node (ref "J14") (pin "K1") (pinfunction "K1_K1") (pintype "passive+no_connect"))
    )
    (net (code "259") (name "unconnected-(J14-PadK7)") (class "Default")
      (node (ref "J14") (pin "K7") (pinfunction "K7_K7") (pintype "passive+no_connect"))
    )
    (net (code "260") (name "unconnected-(J14-PadK8)") (class "Default")
      (node (ref "J14") (pin "K8") (pinfunction "K8_K8") (pintype "passive+no_connect"))
    )
    (net (code "261") (name "unconnected-(J14-PadK10)") (class "Default")
      (node (ref "J14") (pin "K10") (pinfunction "K10_K10") (pintype "passive+no_connect"))
    )
    (net (code "262") (name "unconnected-(J14-PadK11)") (class "Default")
      (node (ref "J14") (pin "K11") (pinfunction "K11_K11") (pintype "passive+no_connect"))
    )
    (net (code "263") (name "unconnected-(J14-PadK13)") (class "Default")
      (node (ref "J14") (pin "K13") (pinfunction "K13_K13") (pintype "passive+no_connect"))
    )
    (net (code "264") (name "unconnected-(J14-PadK14)") (class "Default")
      (node (ref "J14") (pin "K14") (pinfunction "K14_K14") (pintype "passive+no_connect"))
    )
    (net (code "265") (name "unconnected-(J14-PadK16)") (class "Default")
      (node (ref "J14") (pin "K16") (pinfunction "K16_K16") (pintype "passive+no_connect"))
    )
    (net (code "266") (name "unconnected-(J14-PadK17)") (class "Default")
      (node (ref "J14") (pin "K17") (pinfunction "K17_K17") (pintype "passive+no_connect"))
    )
    (net (code "267") (name "unconnected-(J14-PadK19)") (class "Default")
      (node (ref "J14") (pin "K19") (pinfunction "K19_K19") (pintype "passive+no_connect"))
    )
    (net (code "268") (name "unconnected-(J14-PadK20)") (class "Default")
      (node (ref "J14") (pin "K20") (pinfunction "K20_K20") (pintype "passive+no_connect"))
    )
    (net (code "269") (name "unconnected-(J14-PadK22)") (class "Default")
      (node (ref "J14") (pin "K22") (pinfunction "K22_K22") (pintype "passive+no_connect"))
    )
    (net (code "270") (name "unconnected-(J14-PadK23)") (class "Default")
      (node (ref "J14") (pin "K23") (pinfunction "K23_K23") (pintype "passive+no_connect"))
    )
    (net (code "271") (name "unconnected-(J14-PadK25)") (class "Default")
      (node (ref "J14") (pin "K25") (pinfunction "K25_K25") (pintype "passive+no_connect"))
    )
    (net (code "272") (name "unconnected-(J14-PadK26)") (class "Default")
      (node (ref "J14") (pin "K26") (pinfunction "K26_K26") (pintype "passive+no_connect"))
    )
    (net (code "273") (name "unconnected-(J14-PadK28)") (class "Default")
      (node (ref "J14") (pin "K28") (pinfunction "K28_K28") (pintype "passive+no_connect"))
    )
    (net (code "274") (name "unconnected-(J14-PadK29)") (class "Default")
      (node (ref "J14") (pin "K29") (pinfunction "K29_K29") (pintype "passive+no_connect"))
    )
    (net (code "275") (name "unconnected-(J14-PadK31)") (class "Default")
      (node (ref "J14") (pin "K31") (pinfunction "K31_K31") (pintype "passive+no_connect"))
    )
    (net (code "276") (name "unconnected-(J14-PadK32)") (class "Default")
      (node (ref "J14") (pin "K32") (pinfunction "K32_K32") (pintype "passive+no_connect"))
    )
    (net (code "277") (name "unconnected-(J14-PadK34)") (class "Default")
      (node (ref "J14") (pin "K34") (pinfunction "K34_K34") (pintype "passive+no_connect"))
    )
    (net (code "278") (name "unconnected-(J14-PadK35)") (class "Default")
      (node (ref "J14") (pin "K35") (pinfunction "K35_K35") (pintype "passive+no_connect"))
    )
    (net (code "279") (name "unconnected-(J14-PadK37)") (class "Default")
      (node (ref "J14") (pin "K37") (pinfunction "K37_K37") (pintype "passive+no_connect"))
    )
    (net (code "280") (name "unconnected-(J14-PadK38)") (class "Default")
      (node (ref "J14") (pin "K38") (pinfunction "K38_K38") (pintype "passive+no_connect"))
    )
    (net (code "281") (name "unconnected-(J14-PadK40)") (class "Default")
      (node (ref "J14") (pin "K40") (pinfunction "K40_K40") (pintype "passive+no_connect"))
    )
    (net (code "282") (name "unconnected-(U13D-NCHS_IO5_P-Pad218)") (class "Default")
      (node (ref "U13") (pin "218") (pinfunction "NCHS_IO5_P_218") (pintype "input+no_connect"))
    )
    (net (code "283") (name "unconnected-(U13D-NC_HSIO1_N-Pad73)") (class "Default")
      (node (ref "U13") (pin "73") (pinfunction "NC_HSIO1_N_73") (pintype "input+no_connect"))
    )
    (net (code "284") (name "unconnected-(U13D-NC_HSIO1_P-Pad74)") (class "Default")
      (node (ref "U13") (pin "74") (pinfunction "NC_HSIO1_P_74") (pintype "input+no_connect"))
    )
    (net (code "285") (name "unconnected-(U13D-NC_HSIO2_N-Pad109)") (class "Default")
      (node (ref "U13") (pin "109") (pinfunction "NC_HSIO2_N_109") (pintype "input+no_connect"))
    )
    (net (code "286") (name "unconnected-(U13D-NC_HSIO2_P-Pad110)") (class "Default")
      (node (ref "U13") (pin "110") (pinfunction "NC_HSIO2_P_110") (pintype "input+no_connect"))
    )
    (net (code "287") (name "unconnected-(U13D-NC_HSIO3_N-Pad145)") (class "Default")
      (node (ref "U13") (pin "145") (pinfunction "NC_HSIO3_N_145") (pintype "input+no_connect"))
    )
    (net (code "288") (name "unconnected-(U13D-NC_HSIO3_P-Pad146)") (class "Default")
      (node (ref "U13") (pin "146") (pinfunction "NC_HSIO3_P_146") (pintype "input+no_connect"))
    )
    (net (code "289") (name "unconnected-(U13D-NC_HSIO4_N-Pad181)") (class "Default")
      (node (ref "U13") (pin "181") (pinfunction "NC_HSIO4_N_181") (pintype "input+no_connect"))
    )
    (net (code "290") (name "unconnected-(U13D-NC_HSIO4_P-Pad182)") (class "Default")
      (node (ref "U13") (pin "182") (pinfunction "NC_HSIO4_P_182") (pintype "input+no_connect"))
    )
    (net (code "291") (name "unconnected-(U13D-NC_HSIO5_N-Pad217)") (class "Default")
      (node (ref "U13") (pin "217") (pinfunction "NC_HSIO5_N_217") (pintype "input+no_connect"))
    )
    (net (code "292") (name "unconnected-(U13D-NC_HSIO6_N-Pad253)") (class "Default")
      (node (ref "U13") (pin "253") (pinfunction "NC_HSIO6_N_253") (pintype "input+no_connect"))
    )
    (net (code "293") (name "unconnected-(U13D-NC_HSIO6_P-Pad254)") (class "Default")
      (node (ref "U13") (pin "254") (pinfunction "NC_HSIO6_P_254") (pintype "input+no_connect"))
    )
    (net (code "294") (name "unconnected-(U13D-NC_HSIO7_N-Pad71)") (class "Default")
      (node (ref "U13") (pin "71") (pinfunction "NC_HSIO7_N_71") (pintype "input+no_connect"))
    )
    (net (code "295") (name "unconnected-(U13D-NC_HSIO7_P-Pad72)") (class "Default")
      (node (ref "U13") (pin "72") (pinfunction "NC_HSIO7_P_72") (pintype "input+no_connect"))
    )
    (net (code "296") (name "unconnected-(U13D-NC_HSIO8_N-Pad107)") (class "Default")
      (node (ref "U13") (pin "107") (pinfunction "NC_HSIO8_N_107") (pintype "input+no_connect"))
    )
    (net (code "297") (name "unconnected-(U13D-NC_HSIO8_P-Pad108)") (class "Default")
      (node (ref "U13") (pin "108") (pinfunction "NC_HSIO8_P_108") (pintype "input+no_connect"))
    )
    (net (code "298") (name "unconnected-(U13D-NC_HSIO12_N-Pad251)") (class "Default")
      (node (ref "U13") (pin "251") (pinfunction "NC_HSIO12_N_251") (pintype "input+no_connect"))
    )
    (net (code "299") (name "unconnected-(U13D-NC_HSIO12_P-Pad252)") (class "Default")
      (node (ref "U13") (pin "252") (pinfunction "NC_HSIO12_P_252") (pintype "input+no_connect"))
    )
    (net (code "300") (name "unconnected-(U13D-NC_IO1-Pad324)") (class "Default")
      (node (ref "U13") (pin "324") (pinfunction "NC_IO1_324") (pintype "input+no_connect"))
    )
    (net (code "301") (name "unconnected-(U13D-NC_IO2-Pad323)") (class "Default")
      (node (ref "U13") (pin "323") (pinfunction "NC_IO2_323") (pintype "input+no_connect"))
    )
    (net (code "302") (name "unconnected-(U13D-NC_IO3-Pad322)") (class "Default")
      (node (ref "U13") (pin "322") (pinfunction "NC_IO3_322") (pintype "input+no_connect"))
    )
    (net (code "303") (name "unconnected-(U13D-NC_IO4-Pad321)") (class "Default")
      (node (ref "U13") (pin "321") (pinfunction "NC_IO4_321") (pintype "input+no_connect"))
    )
    (net (code "304") (name "unconnected-(U13D-NC_IO5-Pad320)") (class "Default")
      (node (ref "U13") (pin "320") (pinfunction "NC_IO5_320") (pintype "input+no_connect"))
    )
    (net (code "305") (name "unconnected-(U13D-NC_IO6-Pad310)") (class "Default")
      (node (ref "U13") (pin "310") (pinfunction "NC_IO6_310") (pintype "input+no_connect"))
    )
    (net (code "306") (name "unconnected-(U13D-NC_IO7-Pad309)") (class "Default")
      (node (ref "U13") (pin "309") (pinfunction "NC_IO7_309") (pintype "input+no_connect"))
    )
    (net (code "307") (name "unconnected-(U13D-NC_IO8-Pad308)") (class "Default")
      (node (ref "U13") (pin "308") (pinfunction "NC_IO8_308") (pintype "input+no_connect"))
    )
    (net (code "308") (name "unconnected-(U13D-NC_IO9-Pad307)") (class "Default")
      (node (ref "U13") (pin "307") (pinfunction "NC_IO9_307") (pintype "input+no_connect"))
    )
    (net (code "309") (name "unconnected-(U13D-NC_IO10-Pad306)") (class "Default")
      (node (ref "U13") (pin "306") (pinfunction "NC_IO10_306") (pintype "input+no_connect"))
    )
    (net (code "310") (name "unconnected-(U13D-NC_IO11-Pad304)") (class "Default")
      (node (ref "U13") (pin "304") (pinfunction "NC_IO11_304") (pintype "input+no_connect"))
    )
    (net (code "311") (name "unconnected-(U13D-NC_IO12-Pad303)") (class "Default")
      (node (ref "U13") (pin "303") (pinfunction "NC_IO12_303") (pintype "input+no_connect"))
    )
    (net (code "312") (name "unconnected-(U13D-NC_IO13-Pad292)") (class "Default")
      (node (ref "U13") (pin "292") (pinfunction "NC_IO13_292") (pintype "input+no_connect"))
    )
    (net (code "313") (name "unconnected-(U13D-NC_IO14-Pad291)") (class "Default")
      (node (ref "U13") (pin "291") (pinfunction "NC_IO14_291") (pintype "input+no_connect"))
    )
    (net (code "314") (name "unconnected-(U13D-NC_IO15-Pad289)") (class "Default")
      (node (ref "U13") (pin "289") (pinfunction "NC_IO15_289") (pintype "input+no_connect"))
    )
    (net (code "315") (name "unconnected-(U13D-NC_IO16-Pad288)") (class "Default")
      (node (ref "U13") (pin "288") (pinfunction "NC_IO16_288") (pintype "input+no_connect"))
    )
    (net (code "316") (name "unconnected-(U13D-NC_IO17-Pad287)") (class "Default")
      (node (ref "U13") (pin "287") (pinfunction "NC_IO17_287") (pintype "input+no_connect"))
    )
    (net (code "317") (name "unconnected-(U13D-NC_IO18-Pad286)") (class "Default")
      (node (ref "U13") (pin "286") (pinfunction "NC_IO18_286") (pintype "input+no_connect"))
    )
    (net (code "318") (name "unconnected-(U13D-NC_IO19-Pad285)") (class "Default")
      (node (ref "U13") (pin "285") (pinfunction "NC_IO19_285") (pintype "input+no_connect"))
    )
    (net (code "319") (name "unconnected-(U13D-NC_IO20-Pad284)") (class "Default")
      (node (ref "U13") (pin "284") (pinfunction "NC_IO20_284") (pintype "input+no_connect"))
    )
    (net (code "320") (name "unconnected-(U13D-NC_IO21-Pad274)") (class "Default")
      (node (ref "U13") (pin "274") (pinfunction "NC_IO21_274") (pintype "input+no_connect"))
    )
    (net (code "321") (name "unconnected-(U13D-NC_IO22-Pad273)") (class "Default")
      (node (ref "U13") (pin "273") (pinfunction "NC_IO22_273") (pintype "input+no_connect"))
    )
    (net (code "322") (name "unconnected-(U13D-NC_IO23-Pad272)") (class "Default")
      (node (ref "U13") (pin "272") (pinfunction "NC_IO23_272") (pintype "input+no_connect"))
    )
    (net (code "323") (name "unconnected-(U13D-NC_IO24-Pad271)") (class "Default")
      (node (ref "U13") (pin "271") (pinfunction "NC_IO24_271") (pintype "input+no_connect"))
    )
    (net (code "324") (name "unconnected-(U13D-NC_IO25-Pad267)") (class "Default")
      (node (ref "U13") (pin "267") (pinfunction "NC_IO25_267") (pintype "input+no_connect"))
    )
    (net (code "325") (name "unconnected-(U13D-NC_IO26-Pad266)") (class "Default")
      (node (ref "U13") (pin "266") (pinfunction "NC_IO26_266") (pintype "input+no_connect"))
    )
    (net (code "326") (name "unconnected-(U13D-NC_IO27-Pad265)") (class "Default")
      (node (ref "U13") (pin "265") (pinfunction "NC_IO27_265") (pintype "input+no_connect"))
    )
    (net (code "327") (name "unconnected-(U13D-NC_IO28-Pad258)") (class "Default")
      (node (ref "U13") (pin "258") (pinfunction "NC_IO28_258") (pintype "input+no_connect"))
    )
    (net (code "328") (name "unconnected-(U13D-NC_IO29-Pad257)") (class "Default")
      (node (ref "U13") (pin "257") (pinfunction "NC_IO29_257") (pintype "input+no_connect"))
    )
    (net (code "329") (name "unconnected-(U13D-NC_IO30-Pad256)") (class "Default")
      (node (ref "U13") (pin "256") (pinfunction "NC_IO30_256") (pintype "input+no_connect"))
    )
    (net (code "330") (name "unconnected-(U13D-NC_IO31-Pad249)") (class "Default")
      (node (ref "U13") (pin "249") (pinfunction "NC_IO31_249") (pintype "input+no_connect"))
    )
    (net (code "331") (name "unconnected-(U13D-NC_IO32-Pad247)") (class "Default")
      (node (ref "U13") (pin "247") (pinfunction "NC_IO32_247") (pintype "input+no_connect"))
    )
    (net (code "332") (name "unconnected-(U13D-NC_IO33-Pad240)") (class "Default")
      (node (ref "U13") (pin "240") (pinfunction "NC_IO33_240") (pintype "input+no_connect"))
    )
    (net (code "333") (name "unconnected-(U13D-NC_IO34-Pad238)") (class "Default")
      (node (ref "U13") (pin "238") (pinfunction "NC_IO34_238") (pintype "input+no_connect"))
    )
    (net (code "334") (name "unconnected-(U13D-NC_IO35-Pad231)") (class "Default")
      (node (ref "U13") (pin "231") (pinfunction "NC_IO35_231") (pintype "input+no_connect"))
    )
    (net (code "335") (name "unconnected-(U13D-NC_IO36-Pad230)") (class "Default")
      (node (ref "U13") (pin "230") (pinfunction "NC_IO36_230") (pintype "input+no_connect"))
    )
    (net (code "336") (name "unconnected-(U13D-NC_IO37-Pad229)") (class "Default")
      (node (ref "U13") (pin "229") (pinfunction "NC_IO37_229") (pintype "input+no_connect"))
    )
    (net (code "337") (name "unconnected-(U13D-NC_IO38-Pad222)") (class "Default")
      (node (ref "U13") (pin "222") (pinfunction "NC_IO38_222") (pintype "input+no_connect"))
    )
    (net (code "338") (name "unconnected-(U13D-NC_IO39-Pad221)") (class "Default")
      (node (ref "U13") (pin "221") (pinfunction "NC_IO39_221") (pintype "input+no_connect"))
    )
    (net (code "339") (name "unconnected-(U13D-NC_IO40-Pad220)") (class "Default")
      (node (ref "U13") (pin "220") (pinfunction "NC_IO40_220") (pintype "input+no_connect"))
    )
    (net (code "340") (name "unconnected-(U13D-NC_IO41-Pad213)") (class "Default")
      (node (ref "U13") (pin "213") (pinfunction "NC_IO41_213") (pintype "input+no_connect"))
    )
    (net (code "341") (name "unconnected-(U13D-NC_IO42-Pad212)") (class "Default")
      (node (ref "U13") (pin "212") (pinfunction "NC_IO42_212") (pintype "input+no_connect"))
    )
    (net (code "342") (name "unconnected-(U13D-NC_IO43-Pad211)") (class "Default")
      (node (ref "U13") (pin "211") (pinfunction "NC_IO43_211") (pintype "input+no_connect"))
    )
    (net (code "343") (name "unconnected-(U13D-NC_IO44-Pad204)") (class "Default")
      (node (ref "U13") (pin "204") (pinfunction "NC_IO44_204") (pintype "input+no_connect"))
    )
    (net (code "344") (name "unconnected-(U13D-NC_IO45-Pad203)") (class "Default")
      (node (ref "U13") (pin "203") (pinfunction "NC_IO45_203") (pintype "input+no_connect"))
    )
    (net (code "345") (name "unconnected-(U13D-NC_IO46-Pad202)") (class "Default")
      (node (ref "U13") (pin "202") (pinfunction "NC_IO46_202") (pintype "input+no_connect"))
    )
    (net (code "346") (name "unconnected-(U13D-NC_IO47-Pad195)") (class "Default")
      (node (ref "U13") (pin "195") (pinfunction "NC_IO47_195") (pintype "input+no_connect"))
    )
    (net (code "347") (name "unconnected-(U13D-NC_IO48-Pad193)") (class "Default")
      (node (ref "U13") (pin "193") (pinfunction "NC_IO48_193") (pintype "input+no_connect"))
    )
    (net (code "348") (name "unconnected-(U13D-NC_IO49-Pad186)") (class "Default")
      (node (ref "U13") (pin "186") (pinfunction "NC_IO49_186") (pintype "input+no_connect"))
    )
    (net (code "349") (name "unconnected-(U13D-NC_IO50-Pad184)") (class "Default")
      (node (ref "U13") (pin "184") (pinfunction "NC_IO50_184") (pintype "input+no_connect"))
    )
    (net (code "350") (name "unconnected-(U13D-NC_IO51-Pad177)") (class "Default")
      (node (ref "U13") (pin "177") (pinfunction "NC_IO51_177") (pintype "input+no_connect"))
    )
    (net (code "351") (name "unconnected-(U13D-NC_IO52-Pad176)") (class "Default")
      (node (ref "U13") (pin "176") (pinfunction "NC_IO52_176") (pintype "input+no_connect"))
    )
    (net (code "352") (name "unconnected-(U13D-NC_IO53-Pad175)") (class "Default")
      (node (ref "U13") (pin "175") (pinfunction "NC_IO53_175") (pintype "input+no_connect"))
    )
    (net (code "353") (name "unconnected-(U13D-NC_IO54-Pad168)") (class "Default")
      (node (ref "U13") (pin "168") (pinfunction "NC_IO54_168") (pintype "input+no_connect"))
    )
    (net (code "354") (name "unconnected-(U13D-NC_IO55-Pad167)") (class "Default")
      (node (ref "U13") (pin "167") (pinfunction "NC_IO55_167") (pintype "input+no_connect"))
    )
    (net (code "355") (name "unconnected-(U13D-NC_IO56-Pad166)") (class "Default")
      (node (ref "U13") (pin "166") (pinfunction "NC_IO56_166") (pintype "input+no_connect"))
    )
    (net (code "356") (name "unconnected-(U13D-NC_IO57-Pad159)") (class "Default")
      (node (ref "U13") (pin "159") (pinfunction "NC_IO57_159") (pintype "input+no_connect"))
    )
    (net (code "357") (name "unconnected-(U13D-NC_IO58-Pad158)") (class "Default")
      (node (ref "U13") (pin "158") (pinfunction "NC_IO58_158") (pintype "input+no_connect"))
    )
    (net (code "358") (name "unconnected-(U13D-NC_IO59-Pad157)") (class "Default")
      (node (ref "U13") (pin "157") (pinfunction "NC_IO59_157") (pintype "input+no_connect"))
    )
    (net (code "359") (name "unconnected-(U13D-NC_IO60-Pad150)") (class "Default")
      (node (ref "U13") (pin "150") (pinfunction "NC_IO60_150") (pintype "input+no_connect"))
    )
    (net (code "360") (name "unconnected-(U13D-NC_IO61-Pad149)") (class "Default")
      (node (ref "U13") (pin "149") (pinfunction "NC_IO61_149") (pintype "input+no_connect"))
    )
    (net (code "361") (name "unconnected-(U13D-NC_IO62-Pad148)") (class "Default")
      (node (ref "U13") (pin "148") (pinfunction "NC_IO62_148") (pintype "input+no_connect"))
    )
    (net (code "362") (name "unconnected-(U13D-NC_IO63-Pad141)") (class "Default")
      (node (ref "U13") (pin "141") (pinfunction "NC_IO63_141") (pintype "input+no_connect"))
    )
    (net (code "363") (name "unconnected-(U13D-NC_IO64-Pad139)") (class "Default")
      (node (ref "U13") (pin "139") (pinfunction "NC_IO64_139") (pintype "input+no_connect"))
    )
    (net (code "364") (name "unconnected-(U13D-NC_IO65-Pad132)") (class "Default")
      (node (ref "U13") (pin "132") (pinfunction "NC_IO65_132") (pintype "input+no_connect"))
    )
    (net (code "365") (name "unconnected-(U13D-NC_IO66-Pad130)") (class "Default")
      (node (ref "U13") (pin "130") (pinfunction "NC_IO66_130") (pintype "input+no_connect"))
    )
    (net (code "366") (name "unconnected-(U13D-NC_IO67-Pad123)") (class "Default")
      (node (ref "U13") (pin "123") (pinfunction "NC_IO67_123") (pintype "input+no_connect"))
    )
    (net (code "367") (name "unconnected-(U13D-NC_IO68-Pad122)") (class "Default")
      (node (ref "U13") (pin "122") (pinfunction "NC_IO68_122") (pintype "input+no_connect"))
    )
    (net (code "368") (name "unconnected-(U13D-NC_IO69-Pad121)") (class "Default")
      (node (ref "U13") (pin "121") (pinfunction "NC_IO69_121") (pintype "input+no_connect"))
    )
    (net (code "369") (name "unconnected-(U13D-NC_IO70-Pad114)") (class "Default")
      (node (ref "U13") (pin "114") (pinfunction "NC_IO70_114") (pintype "input+no_connect"))
    )
    (net (code "370") (name "unconnected-(U13D-NC_IO71-Pad113)") (class "Default")
      (node (ref "U13") (pin "113") (pinfunction "NC_IO71_113") (pintype "input+no_connect"))
    )
    (net (code "371") (name "unconnected-(U13D-NC_IO72-Pad112)") (class "Default")
      (node (ref "U13") (pin "112") (pinfunction "NC_IO72_112") (pintype "input+no_connect"))
    )
    (net (code "372") (name "unconnected-(U13D-NC_IO73-Pad105)") (class "Default")
      (node (ref "U13") (pin "105") (pinfunction "NC_IO73_105") (pintype "input+no_connect"))
    )
    (net (code "373") (name "unconnected-(U13D-NC_IO74-Pad104)") (class "Default")
      (node (ref "U13") (pin "104") (pinfunction "NC_IO74_104") (pintype "input+no_connect"))
    )
    (net (code "374") (name "unconnected-(U13D-NC_IO75-Pad103)") (class "Default")
      (node (ref "U13") (pin "103") (pinfunction "NC_IO75_103") (pintype "input+no_connect"))
    )
    (net (code "375") (name "unconnected-(U13D-NC_IO76-Pad96)") (class "Default")
      (node (ref "U13") (pin "96") (pinfunction "NC_IO76_96") (pintype "input+no_connect"))
    )
    (net (code "376") (name "unconnected-(U13D-NC_IO77-Pad95)") (class "Default")
      (node (ref "U13") (pin "95") (pinfunction "NC_IO77_95") (pintype "input+no_connect"))
    )
    (net (code "377") (name "unconnected-(U13D-NC_IO78-Pad94)") (class "Default")
      (node (ref "U13") (pin "94") (pinfunction "NC_IO78_94") (pintype "input+no_connect"))
    )
    (net (code "378") (name "unconnected-(U13D-NC_IO79-Pad87)") (class "Default")
      (node (ref "U13") (pin "87") (pinfunction "NC_IO79_87") (pintype "input+no_connect"))
    )
    (net (code "379") (name "unconnected-(U13D-NC_IO80-Pad85)") (class "Default")
      (node (ref "U13") (pin "85") (pinfunction "NC_IO80_85") (pintype "input+no_connect"))
    )
    (net (code "380") (name "unconnected-(U13D-NC_IO81-Pad78)") (class "Default")
      (node (ref "U13") (pin "78") (pinfunction "NC_IO81_78") (pintype "input+no_connect"))
    )
    (net (code "381") (name "unconnected-(U13D-NC_IO82-Pad76)") (class "Default")
      (node (ref "U13") (pin "76") (pinfunction "NC_IO82_76") (pintype "input+no_connect"))
    )
    (net (code "382") (name "unconnected-(U13D-NC_IO83-Pad69)") (class "Default")
      (node (ref "U13") (pin "69") (pinfunction "NC_IO83_69") (pintype "input+no_connect"))
    )
    (net (code "383") (name "unconnected-(U13D-NC_IO84-Pad68)") (class "Default")
      (node (ref "U13") (pin "68") (pinfunction "NC_IO84_68") (pintype "input+no_connect"))
    )
    (net (code "384") (name "unconnected-(U13D-NC_IO85-Pad67)") (class "Default")
      (node (ref "U13") (pin "67") (pinfunction "NC_IO85_67") (pintype "input+no_connect"))
    )
    (net (code "385") (name "unconnected-(U13D-NC_IO86-Pad60)") (class "Default")
      (node (ref "U13") (pin "60") (pinfunction "NC_IO86_60") (pintype "input+no_connect"))
    )
    (net (code "386") (name "unconnected-(U13D-NC_IO87-Pad59)") (class "Default")
      (node (ref "U13") (pin "59") (pinfunction "NC_IO87_59") (pintype "input+no_connect"))
    )
    (net (code "387") (name "unconnected-(U13D-NC_IO88-Pad58)") (class "Default")
      (node (ref "U13") (pin "58") (pinfunction "NC_IO88_58") (pintype "input+no_connect"))
    )
    (net (code "388") (name "unconnected-(U13D-NC_IO89-Pad54)") (class "Default")
      (node (ref "U13") (pin "54") (pinfunction "NC_IO89_54") (pintype "input+no_connect"))
    )
    (net (code "389") (name "unconnected-(U13D-NC_IO90-Pad53)") (class "Default")
      (node (ref "U13") (pin "53") (pinfunction "NC_IO90_53") (pintype "input+no_connect"))
    )
    (net (code "390") (name "unconnected-(U13D-NC_IO91-Pad52)") (class "Default")
      (node (ref "U13") (pin "52") (pinfunction "NC_IO91_52") (pintype "input+no_connect"))
    )
    (net (code "391") (name "unconnected-(U13D-NC_IO92-Pad51)") (class "Default")
      (node (ref "U13") (pin "51") (pinfunction "NC_IO92_51") (pintype "input+no_connect"))
    )
    (net (code "392") (name "unconnected-(U13D-NC_IO93-Pad40)") (class "Default")
      (node (ref "U13") (pin "40") (pinfunction "NC_IO93_40") (pintype "input+no_connect"))
    )
    (net (code "393") (name "unconnected-(U13D-NC_IO94-Pad39)") (class "Default")
      (node (ref "U13") (pin "39") (pinfunction "NC_IO94_39") (pintype "input+no_connect"))
    )
    (net (code "394") (name "unconnected-(U13D-NC_IO95-Pad38)") (class "Default")
      (node (ref "U13") (pin "38") (pinfunction "NC_IO95_38") (pintype "input+no_connect"))
    )
    (net (code "395") (name "unconnected-(U13D-NC_IO96-Pad37)") (class "Default")
      (node (ref "U13") (pin "37") (pinfunction "NC_IO96_37") (pintype "input+no_connect"))
    )
    (net (code "396") (name "unconnected-(U13D-NC_IO97-Pad36)") (class "Default")
      (node (ref "U13") (pin "36") (pinfunction "NC_IO97_36") (pintype "input+no_connect"))
    )
    (net (code "397") (name "unconnected-(U13D-NC_IO98-Pad34)") (class "Default")
      (node (ref "U13") (pin "34") (pinfunction "NC_IO98_34") (pintype "input+no_connect"))
    )
    (net (code "398") (name "unconnected-(U13D-NC_IO99-Pad33)") (class "Default")
      (node (ref "U13") (pin "33") (pinfunction "NC_IO99_33") (pintype "input+no_connect"))
    )
    (net (code "399") (name "unconnected-(U13D-NC_IO100-Pad22)") (class "Default")
      (node (ref "U13") (pin "22") (pinfunction "NC_IO100_22") (pintype "input+no_connect"))
    )
    (net (code "400") (name "unconnected-(U13D-NC_IO101-Pad21)") (class "Default")
      (node (ref "U13") (pin "21") (pinfunction "NC_IO101_21") (pintype "input+no_connect"))
    )
    (net (code "401") (name "unconnected-(U13D-NC_IO102-Pad19)") (class "Default")
      (node (ref "U13") (pin "19") (pinfunction "NC_IO102_19") (pintype "input+no_connect"))
    )
    (net (code "402") (name "unconnected-(U13D-NC_IO103-Pad18)") (class "Default")
      (node (ref "U13") (pin "18") (pinfunction "NC_IO103_18") (pintype "input+no_connect"))
    )
    (net (code "403") (name "unconnected-(U13D-NC_IO104-Pad17)") (class "Default")
      (node (ref "U13") (pin "17") (pinfunction "NC_IO104_17") (pintype "input+no_connect"))
    )
    (net (code "404") (name "unconnected-(U13D-NC_IO105-Pad16)") (class "Default")
      (node (ref "U13") (pin "16") (pinfunction "NC_IO105_16") (pintype "input+no_connect"))
    )
    (net (code "405") (name "unconnected-(U13D-NC_IO106-Pad15)") (class "Default")
      (node (ref "U13") (pin "15") (pinfunction "NC_IO106_15") (pintype "input+no_connect"))
    )
    (net (code "406") (name "unconnected-(U13D-NC_IO107-Pad4)") (class "Default")
      (node (ref "U13") (pin "4") (pinfunction "NC_IO107_4") (pintype "input+no_connect"))
    )
    (net (code "407") (name "unconnected-(U13D-NC_IO108-Pad3)") (class "Default")
      (node (ref "U13") (pin "3") (pinfunction "NC_IO108_3") (pintype "input+no_connect"))
    )
    (net (code "408") (name "unconnected-(U13D-NC_IO109-Pad2)") (class "Default")
      (node (ref "U13") (pin "2") (pinfunction "NC_IO109_2") (pintype "input+no_connect"))
    )
    (net (code "409") (name "unconnected-(U13D-NC_IO110-Pad1)") (class "Default")
      (node (ref "U13") (pin "1") (pinfunction "NC_IO110_1") (pintype "input+no_connect"))
    )
    (net (code "410") (name "unconnected-(U13D-NC_VDD_G9-Pad208)") (class "Default")
      (node (ref "U13") (pin "208") (pinfunction "NC_VDD_G9_208") (pintype "input+no_connect"))
    )
    (net (code "411") (name "unconnected-(U13D-NC_VDD_G10-Pad207)") (class "Default")
      (node (ref "U13") (pin "207") (pinfunction "NC_VDD_G10_207") (pintype "input+no_connect"))
    )
    (net (code "412") (name "unconnected-(U13D-NC_VDD_H11-Pad188)") (class "Default")
      (node (ref "U13") (pin "188") (pinfunction "NC_VDD_H11_188") (pintype "input+no_connect"))
    )
  )
)
